# hand_main_v2.net
KiCad netlist of a schematic drawn in Altium Designer
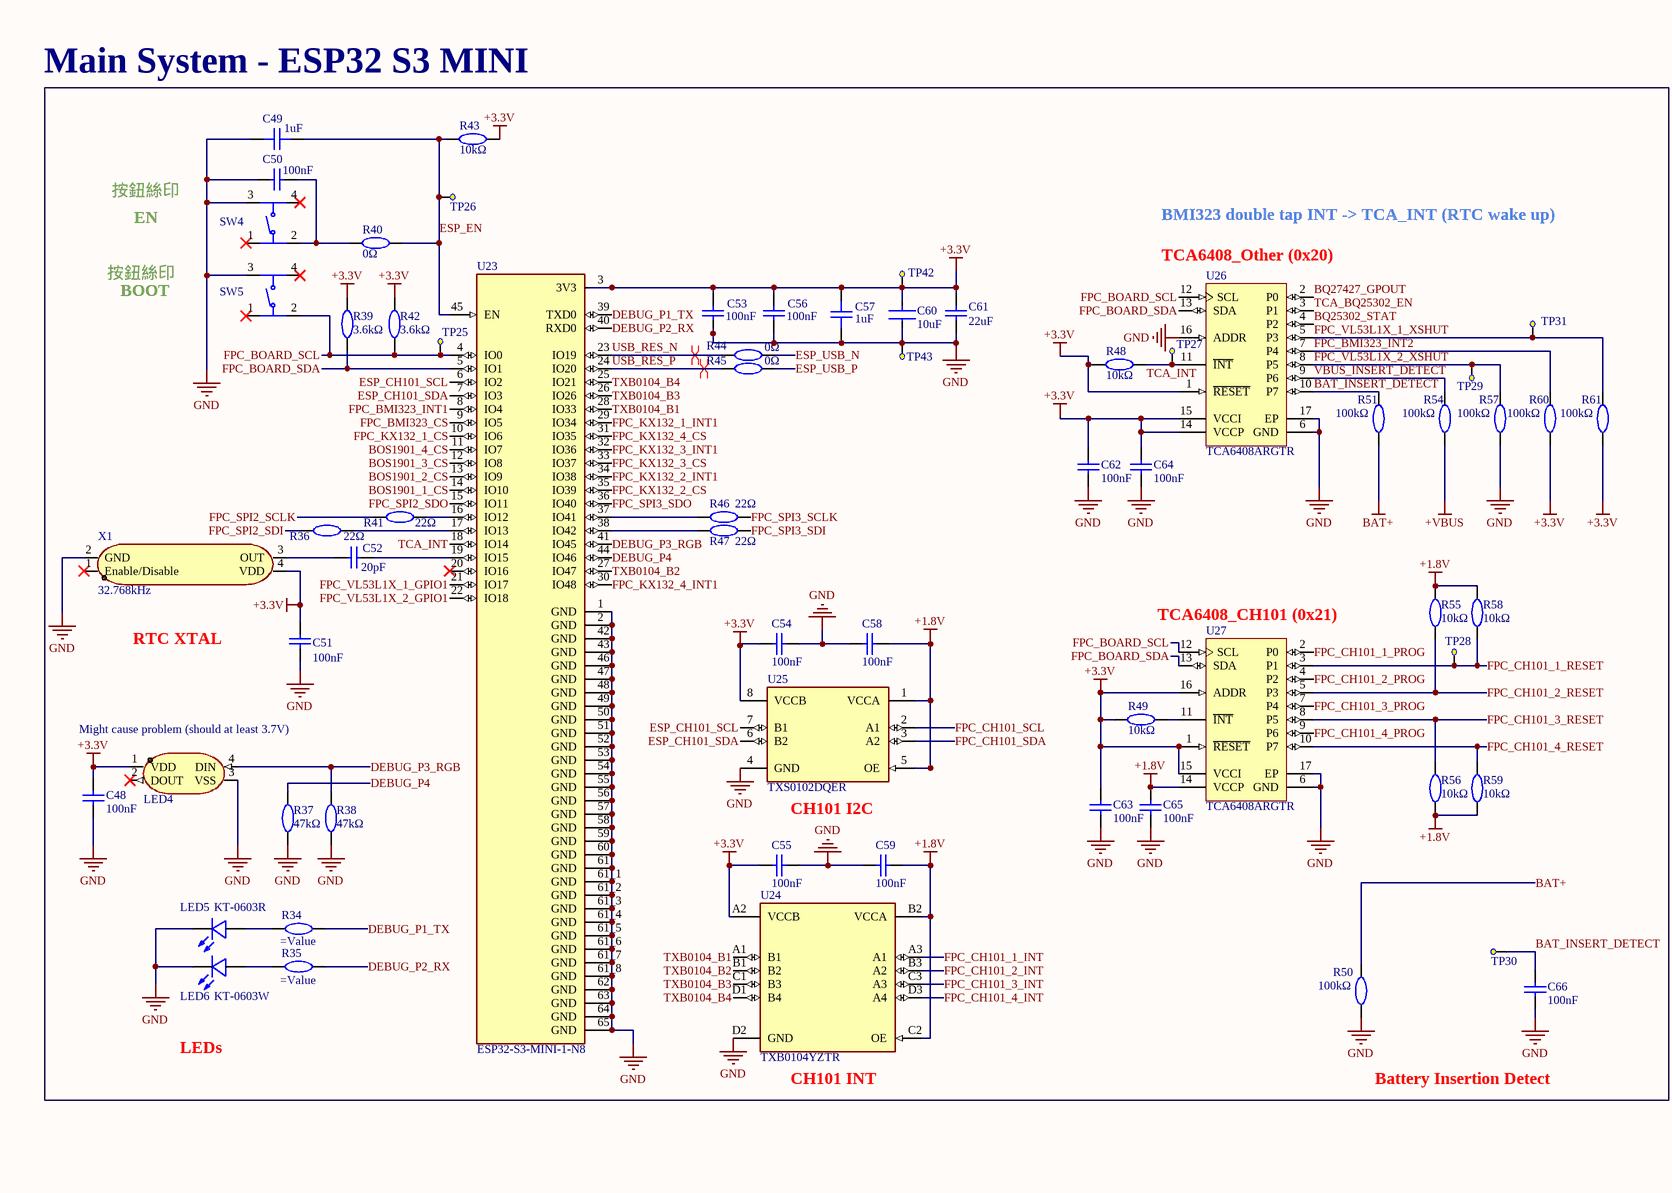
[diagram p0: hand_main_v2.SchDoc, left]
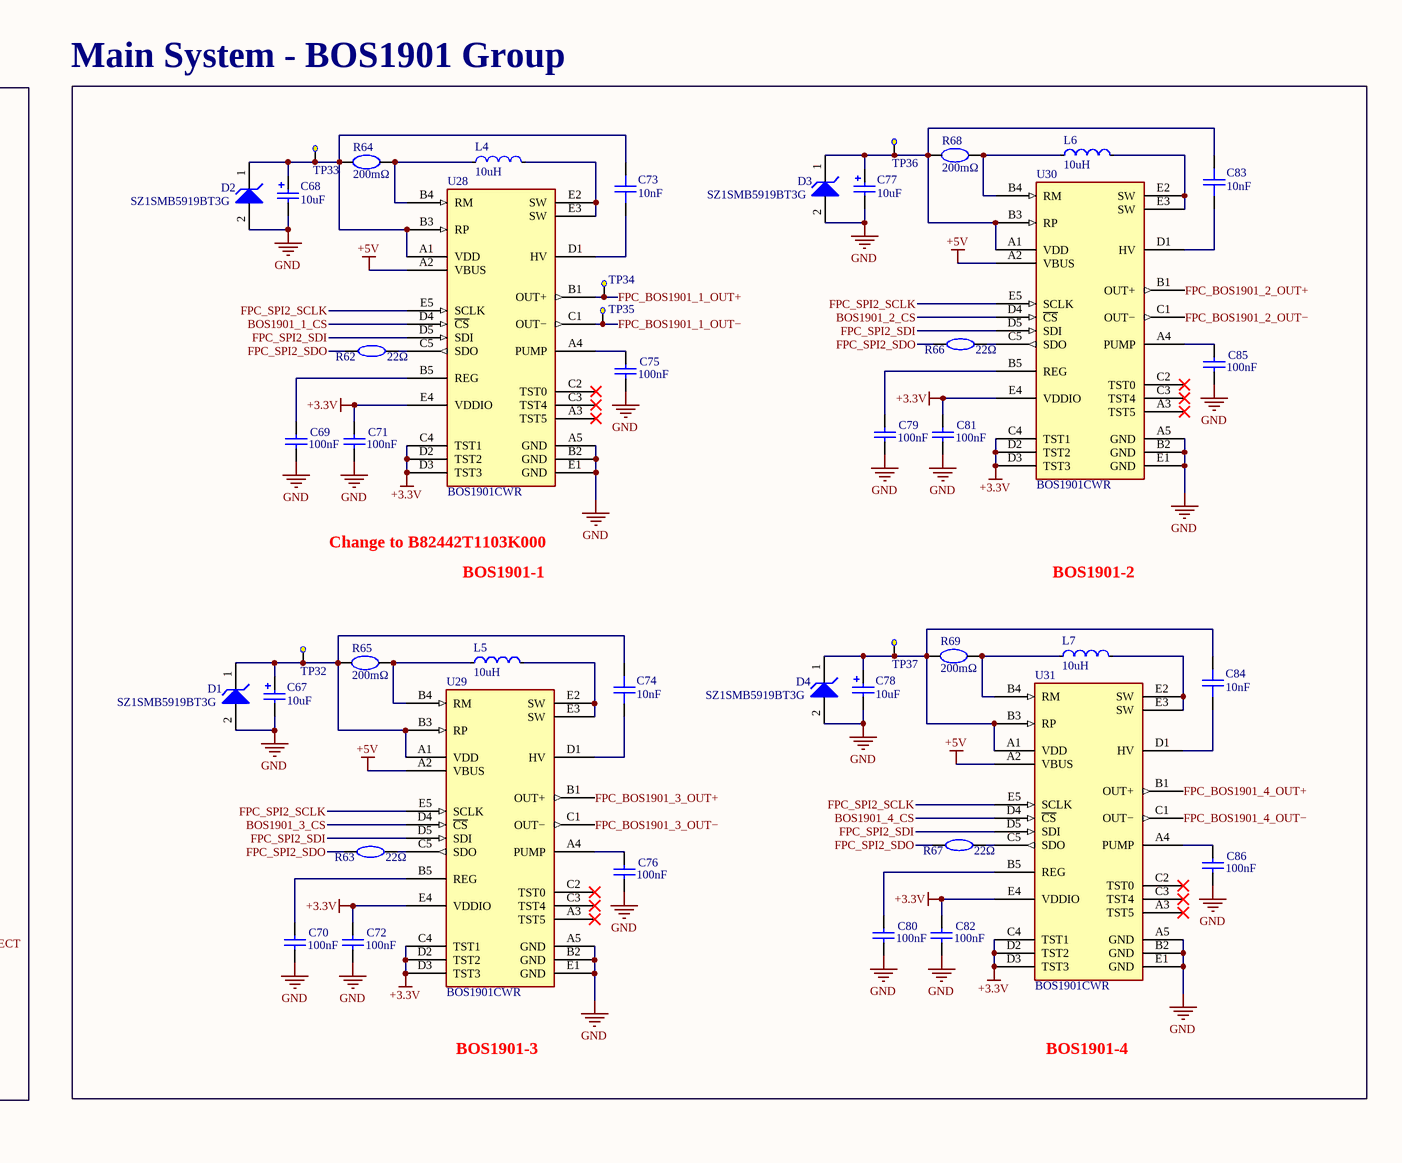
[diagram p1: hand_main_v2.SchDoc, middle]
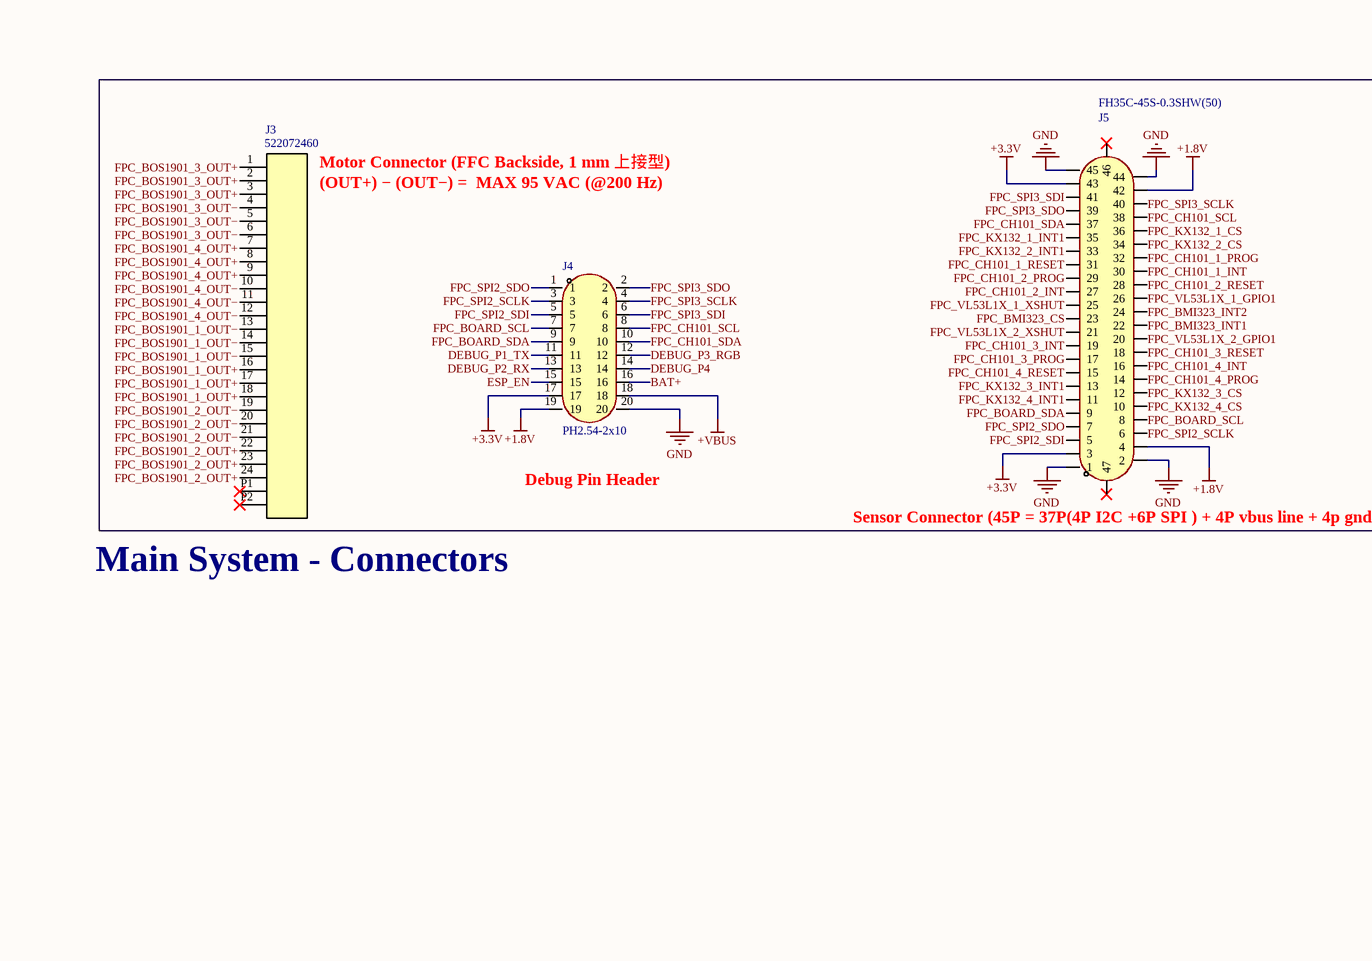
[diagram p2: hand_main_v2.SchDoc, right]

(export (version "E")
  (design (tool "Eeschema 10.0.6"))
  (components
    (comp (ref "C48")
      (value "100nF")
      (footprint "CAPC1050X55X23NL05T13")
      (description "Chip Capacitor, 100 nF, +/- 10%, 16 V, -55 to 125 degC, 0402 (1005 Metric), RoHS, Tape and Reel")
      (fields (field (name "MANUFACTURER") "Samsung Electro-Mechanics"))
      (libsource (lib "hand_ad_lib") (part "CL05B104KO5NNNC"))
    )
    (comp (ref "C49")
      (value "1uF")
      (footprint "C0402")
      (description "MLCC, 1 uF, 25 V, ± 10%, X5R, 0402 [1005 Metric]")
      (fields
        (field (name "MANUFACTURER") "SAMSUNG(三星)")
        (field (name "MANUFACTURER PART") "CL05A105KA5NQNC")
        (field (name "NAME") "1uF")
      )
      (libsource (lib "hand_ad_lib") (part "CL05A105KA5NQNC"))
    )
    (comp (ref "C50")
      (value "100nF")
      (footprint "CAPC1050X55X23NL05T13")
      (description "Chip Capacitor, 100 nF, +/- 10%, 16 V, -55 to 125 degC, 0402 (1005 Metric), RoHS, Tape and Reel")
      (fields (field (name "MANUFACTURER") "Samsung Electro-Mechanics"))
      (libsource (lib "hand_ad_lib") (part "CL05B104KO5NNNC"))
    )
    (comp (ref "C51")
      (value "100nF")
      (footprint "CAPC1050X55X23NL05T13")
      (description "Chip Capacitor, 100 nF, +/- 10%, 16 V, -55 to 125 degC, 0402 (1005 Metric), RoHS, Tape and Reel")
      (fields (field (name "MANUFACTURER") "Samsung Electro-Mechanics"))
      (libsource (lib "hand_ad_lib") (part "CL05B104KO5NNNC"))
    )
    (comp (ref "C52")
      (value "20pF")
      (footprint "C0603")
      (description "MLCC, 20pF, 50 V, ± 5%, C0G, 0603 [1608 Metric]")
      (fields
        (field (name "MANUFACTURER") "SAMSUNG(三星)")
        (field (name "MANUFACTURER PART") "CL10C200JB8NNNC")
        (field (name "NAME") "20pF")
      )
      (libsource (lib "hand_ad_lib") (part "CL10C200JB8NNNC"))
    )
    (comp (ref "C53")
      (value "100nF")
      (footprint "CAPC1050X55X23NL05T13")
      (description "Chip Capacitor, 100 nF, +/- 10%, 16 V, -55 to 125 degC, 0402 (1005 Metric), RoHS, Tape and Reel")
      (fields (field (name "MANUFACTURER") "Samsung Electro-Mechanics"))
      (libsource (lib "hand_ad_lib") (part "CL05B104KO5NNNC"))
    )
    (comp (ref "C54")
      (value "100nF")
      (footprint "CAPC1050X55X23NL05T13")
      (description "Chip Capacitor, 100 nF, +/- 10%, 16 V, -55 to 125 degC, 0402 (1005 Metric), RoHS, Tape and Reel")
      (fields (field (name "MANUFACTURER") "Samsung Electro-Mechanics"))
      (libsource (lib "hand_ad_lib") (part "CL05B104KO5NNNC"))
    )
    (comp (ref "C55")
      (value "100nF")
      (footprint "CAPC1050X55X23NL05T13")
      (description "Chip Capacitor, 100 nF, +/- 10%, 16 V, -55 to 125 degC, 0402 (1005 Metric), RoHS, Tape and Reel")
      (fields (field (name "MANUFACTURER") "Samsung Electro-Mechanics"))
      (libsource (lib "hand_ad_lib") (part "CL05B104KO5NNNC"))
    )
    (comp (ref "C56")
      (value "100nF")
      (footprint "CAPC1050X55X23NL05T13")
      (description "Chip Capacitor, 100 nF, +/- 10%, 16 V, -55 to 125 degC, 0402 (1005 Metric), RoHS, Tape and Reel")
      (fields (field (name "MANUFACTURER") "Samsung Electro-Mechanics"))
      (libsource (lib "hand_ad_lib") (part "CL05B104KO5NNNC"))
    )
    (comp (ref "C57")
      (value "1uF")
      (footprint "C0402")
      (description "MLCC, 1 uF, 25 V, ± 10%, X5R, 0402 [1005 Metric]")
      (fields
        (field (name "MANUFACTURER") "SAMSUNG(三星)")
        (field (name "MANUFACTURER PART") "CL05A105KA5NQNC")
        (field (name "NAME") "1uF")
      )
      (libsource (lib "hand_ad_lib") (part "CL05A105KA5NQNC"))
    )
    (comp (ref "C58")
      (value "100nF")
      (footprint "CAPC1050X55X23NL05T13")
      (description "Chip Capacitor, 100 nF, +/- 10%, 16 V, -55 to 125 degC, 0402 (1005 Metric), RoHS, Tape and Reel")
      (fields (field (name "MANUFACTURER") "Samsung Electro-Mechanics"))
      (libsource (lib "hand_ad_lib") (part "CL05B104KO5NNNC"))
    )
    (comp (ref "C59")
      (value "100nF")
      (footprint "CAPC1050X55X23NL05T13")
      (description "Chip Capacitor, 100 nF, +/- 10%, 16 V, -55 to 125 degC, 0402 (1005 Metric), RoHS, Tape and Reel")
      (fields (field (name "MANUFACTURER") "Samsung Electro-Mechanics"))
      (libsource (lib "hand_ad_lib") (part "CL05B104KO5NNNC"))
    )
    (comp (ref "C60")
      (value "10uF")
      (footprint "FP-CL10-IPC_A")
      (description "Cap Ceramic 10uF 25V X5R ±20% Pad SMD 0603 +85°C T/R")
      (fields (field (name "TOLERANCE") "20%"))
      (libsource (lib "hand_ad_lib") (part "CL10A106MA8NRNC"))
    )
    (comp (ref "C61")
      (value "22uF")
      (footprint "CAPC2013X140X45ML15T25")
      (description "Multi-layer Ceramic Capacitor, 22 uF, -55 to 85 degC, 2-Pin SMD (0805), RoHS, Tape and Reel")
      (fields (field (name "MANUFACTURER") "Samsung Electro-Mechanics") (field (name "TOLERANCE") "±20%"))
      (libsource (lib "hand_ad_lib") (part "CL21A226MAQNNNE"))
    )
    (comp (ref "C62")
      (value "100nF")
      (footprint "CAPC1050X55X23NL05T13")
      (description "Chip Capacitor, 100 nF, +/- 10%, 16 V, -55 to 125 degC, 0402 (1005 Metric), RoHS, Tape and Reel")
      (fields (field (name "MANUFACTURER") "Samsung Electro-Mechanics"))
      (libsource (lib "hand_ad_lib") (part "CL05B104KO5NNNC"))
    )
    (comp (ref "C63")
      (value "100nF")
      (footprint "CAPC1050X55X23NL05T13")
      (description "Chip Capacitor, 100 nF, +/- 10%, 16 V, -55 to 125 degC, 0402 (1005 Metric), RoHS, Tape and Reel")
      (fields (field (name "MANUFACTURER") "Samsung Electro-Mechanics"))
      (libsource (lib "hand_ad_lib") (part "CL05B104KO5NNNC"))
    )
    (comp (ref "C64")
      (value "100nF")
      (footprint "CAPC1050X55X23NL05T13")
      (description "Chip Capacitor, 100 nF, +/- 10%, 16 V, -55 to 125 degC, 0402 (1005 Metric), RoHS, Tape and Reel")
      (fields (field (name "MANUFACTURER") "Samsung Electro-Mechanics"))
      (libsource (lib "hand_ad_lib") (part "CL05B104KO5NNNC"))
    )
    (comp (ref "C65")
      (value "100nF")
      (footprint "CAPC1050X55X23NL05T13")
      (description "Chip Capacitor, 100 nF, +/- 10%, 16 V, -55 to 125 degC, 0402 (1005 Metric), RoHS, Tape and Reel")
      (fields (field (name "MANUFACTURER") "Samsung Electro-Mechanics"))
      (libsource (lib "hand_ad_lib") (part "CL05B104KO5NNNC"))
    )
    (comp (ref "C66")
      (value "100nF")
      (footprint "CAPC1050X55X23NL05T13")
      (description "Chip Capacitor, 100 nF, +/- 10%, 16 V, -55 to 125 degC, 0402 (1005 Metric), RoHS, Tape and Reel")
      (fields (field (name "MANUFACTURER") "Samsung Electro-Mechanics"))
      (libsource (lib "hand_ad_lib") (part "CL05B104KO5NNNC"))
    )
    (comp (ref "C67")
      (value "10uF")
      (footprint "CAP-SMD_L3.2-W1.6-RD-C7171")
      (fields
        (field (name "MANUFACTURER") "Kyocera AVX")
        (field (name "MANUFACTURER PART") "TAJA106K016RNJ")
        (field (name "TOLERANCE") "±10%")
        (field (name "NAME") "10uF")
      )
      (libsource (lib "hand_ad_lib") (part "TAJA106K016RNJ"))
    )
    (comp (ref "C68")
      (value "10uF")
      (footprint "CAP-SMD_L3.2-W1.6-RD-C7171")
      (fields
        (field (name "MANUFACTURER") "Kyocera AVX")
        (field (name "MANUFACTURER PART") "TAJA106K016RNJ")
        (field (name "TOLERANCE") "±10%")
        (field (name "NAME") "10uF")
      )
      (libsource (lib "hand_ad_lib") (part "TAJA106K016RNJ"))
    )
    (comp (ref "C69")
      (value "100nF")
      (footprint "CAPC1050X55X23NL05T13")
      (description "Chip Capacitor, 100 nF, +/- 10%, 16 V, -55 to 125 degC, 0402 (1005 Metric), RoHS, Tape and Reel")
      (fields (field (name "MANUFACTURER") "Samsung Electro-Mechanics"))
      (libsource (lib "hand_ad_lib") (part "CL05B104KO5NNNC"))
    )
    (comp (ref "C70")
      (value "100nF")
      (footprint "CAPC1050X55X23NL05T13")
      (description "Chip Capacitor, 100 nF, +/- 10%, 16 V, -55 to 125 degC, 0402 (1005 Metric), RoHS, Tape and Reel")
      (fields (field (name "MANUFACTURER") "Samsung Electro-Mechanics"))
      (libsource (lib "hand_ad_lib") (part "CL05B104KO5NNNC"))
    )
    (comp (ref "C71")
      (value "100nF")
      (footprint "CAPC1050X55X23NL05T13")
      (description "Chip Capacitor, 100 nF, +/- 10%, 16 V, -55 to 125 degC, 0402 (1005 Metric), RoHS, Tape and Reel")
      (fields (field (name "MANUFACTURER") "Samsung Electro-Mechanics"))
      (libsource (lib "hand_ad_lib") (part "CL05B104KO5NNNC"))
    )
    (comp (ref "C72")
      (value "100nF")
      (footprint "CAPC1050X55X23NL05T13")
      (description "Chip Capacitor, 100 nF, +/- 10%, 16 V, -55 to 125 degC, 0402 (1005 Metric), RoHS, Tape and Reel")
      (fields (field (name "MANUFACTURER") "Samsung Electro-Mechanics"))
      (libsource (lib "hand_ad_lib") (part "CL05B104KO5NNNC"))
    )
    (comp (ref "C73")
      (value "10nF")
      (footprint "C1206")
      (description "Cap Ceramic 0.01uF 250V C0G 5% SMD 1206 125°C Embossed T/R")
      (fields
        (field (name "MANUFACTURER") "muRata(村田)")
        (field (name "MANUFACTURER PART") "GCM31B5C2E103JX01L")
        (field (name "NAME") "10nF")
      )
      (libsource (lib "hand_ad_lib") (part "GCM31B5C2E103JX01L"))
    )
    (comp (ref "C74")
      (value "10nF")
      (footprint "C1206")
      (description "Cap Ceramic 0.01uF 250V C0G 5% SMD 1206 125°C Embossed T/R")
      (fields
        (field (name "MANUFACTURER") "muRata(村田)")
        (field (name "MANUFACTURER PART") "GCM31B5C2E103JX01L")
        (field (name "NAME") "10nF")
      )
      (libsource (lib "hand_ad_lib") (part "GCM31B5C2E103JX01L"))
    )
    (comp (ref "C75")
      (value "100nF")
      (footprint "CAPC1050X55X23NL05T13")
      (description "Chip Capacitor, 100 nF, +/- 10%, 16 V, -55 to 125 degC, 0402 (1005 Metric), RoHS, Tape and Reel")
      (fields (field (name "MANUFACTURER") "Samsung Electro-Mechanics"))
      (libsource (lib "hand_ad_lib") (part "CL05B104KO5NNNC"))
    )
    (comp (ref "C76")
      (value "100nF")
      (footprint "CAPC1050X55X23NL05T13")
      (description "Chip Capacitor, 100 nF, +/- 10%, 16 V, -55 to 125 degC, 0402 (1005 Metric), RoHS, Tape and Reel")
      (fields (field (name "MANUFACTURER") "Samsung Electro-Mechanics"))
      (libsource (lib "hand_ad_lib") (part "CL05B104KO5NNNC"))
    )
    (comp (ref "C77")
      (value "10uF")
      (footprint "CAP-SMD_L3.2-W1.6-RD-C7171")
      (fields
        (field (name "MANUFACTURER") "Kyocera AVX")
        (field (name "MANUFACTURER PART") "TAJA106K016RNJ")
        (field (name "TOLERANCE") "±10%")
        (field (name "NAME") "10uF")
      )
      (libsource (lib "hand_ad_lib") (part "TAJA106K016RNJ"))
    )
    (comp (ref "C78")
      (value "10uF")
      (footprint "CAP-SMD_L3.2-W1.6-RD-C7171")
      (fields
        (field (name "MANUFACTURER") "Kyocera AVX")
        (field (name "MANUFACTURER PART") "TAJA106K016RNJ")
        (field (name "TOLERANCE") "±10%")
        (field (name "NAME") "10uF")
      )
      (libsource (lib "hand_ad_lib") (part "TAJA106K016RNJ"))
    )
    (comp (ref "C79")
      (value "100nF")
      (footprint "CAPC1050X55X23NL05T13")
      (description "Chip Capacitor, 100 nF, +/- 10%, 16 V, -55 to 125 degC, 0402 (1005 Metric), RoHS, Tape and Reel")
      (fields (field (name "MANUFACTURER") "Samsung Electro-Mechanics"))
      (libsource (lib "hand_ad_lib") (part "CL05B104KO5NNNC"))
    )
    (comp (ref "C80")
      (value "100nF")
      (footprint "CAPC1050X55X23NL05T13")
      (description "Chip Capacitor, 100 nF, +/- 10%, 16 V, -55 to 125 degC, 0402 (1005 Metric), RoHS, Tape and Reel")
      (fields (field (name "MANUFACTURER") "Samsung Electro-Mechanics"))
      (libsource (lib "hand_ad_lib") (part "CL05B104KO5NNNC"))
    )
    (comp (ref "C81")
      (value "100nF")
      (footprint "CAPC1050X55X23NL05T13")
      (description "Chip Capacitor, 100 nF, +/- 10%, 16 V, -55 to 125 degC, 0402 (1005 Metric), RoHS, Tape and Reel")
      (fields (field (name "MANUFACTURER") "Samsung Electro-Mechanics"))
      (libsource (lib "hand_ad_lib") (part "CL05B104KO5NNNC"))
    )
    (comp (ref "C82")
      (value "100nF")
      (footprint "CAPC1050X55X23NL05T13")
      (description "Chip Capacitor, 100 nF, +/- 10%, 16 V, -55 to 125 degC, 0402 (1005 Metric), RoHS, Tape and Reel")
      (fields (field (name "MANUFACTURER") "Samsung Electro-Mechanics"))
      (libsource (lib "hand_ad_lib") (part "CL05B104KO5NNNC"))
    )
    (comp (ref "C83")
      (value "10nF")
      (footprint "C1206")
      (description "Cap Ceramic 0.01uF 250V C0G 5% SMD 1206 125°C Embossed T/R")
      (fields
        (field (name "MANUFACTURER") "muRata(村田)")
        (field (name "MANUFACTURER PART") "GCM31B5C2E103JX01L")
        (field (name "NAME") "10nF")
      )
      (libsource (lib "hand_ad_lib") (part "GCM31B5C2E103JX01L"))
    )
    (comp (ref "C84")
      (value "10nF")
      (footprint "C1206")
      (description "Cap Ceramic 0.01uF 250V C0G 5% SMD 1206 125°C Embossed T/R")
      (fields
        (field (name "MANUFACTURER") "muRata(村田)")
        (field (name "MANUFACTURER PART") "GCM31B5C2E103JX01L")
        (field (name "NAME") "10nF")
      )
      (libsource (lib "hand_ad_lib") (part "GCM31B5C2E103JX01L"))
    )
    (comp (ref "C85")
      (value "100nF")
      (footprint "CAPC1050X55X23NL05T13")
      (description "Chip Capacitor, 100 nF, +/- 10%, 16 V, -55 to 125 degC, 0402 (1005 Metric), RoHS, Tape and Reel")
      (fields (field (name "MANUFACTURER") "Samsung Electro-Mechanics"))
      (libsource (lib "hand_ad_lib") (part "CL05B104KO5NNNC"))
    )
    (comp (ref "C86")
      (value "100nF")
      (footprint "CAPC1050X55X23NL05T13")
      (description "Chip Capacitor, 100 nF, +/- 10%, 16 V, -55 to 125 degC, 0402 (1005 Metric), RoHS, Tape and Reel")
      (fields (field (name "MANUFACTURER") "Samsung Electro-Mechanics"))
      (libsource (lib "hand_ad_lib") (part "CL05B104KO5NNNC"))
    )
    (comp (ref "D1")
      (value "SZ1SMB5919BT3G")
      (footprint "ONSC-SMB-2-403A-03_H_V")
      (description "3 W Zener Voltage Regulator, 2-Pin SMB, Pb-Free, Tape and Reel")
      (fields (field (name "MANUFACTURER") "On Semiconductor"))
      (libsource (lib "hand_ad_lib") (part "SZ1SMB5919BT3G"))
    )
    (comp (ref "D2")
      (value "SZ1SMB5919BT3G")
      (footprint "ONSC-SMB-2-403A-03_H_V")
      (description "3 W Zener Voltage Regulator, 2-Pin SMB, Pb-Free, Tape and Reel")
      (fields (field (name "MANUFACTURER") "On Semiconductor"))
      (libsource (lib "hand_ad_lib") (part "SZ1SMB5919BT3G"))
    )
    (comp (ref "D3")
      (value "SZ1SMB5919BT3G")
      (footprint "ONSC-SMB-2-403A-03_H_V")
      (description "3 W Zener Voltage Regulator, 2-Pin SMB, Pb-Free, Tape and Reel")
      (fields (field (name "MANUFACTURER") "On Semiconductor"))
      (libsource (lib "hand_ad_lib") (part "SZ1SMB5919BT3G"))
    )
    (comp (ref "D4")
      (value "SZ1SMB5919BT3G")
      (footprint "ONSC-SMB-2-403A-03_H_V")
      (description "3 W Zener Voltage Regulator, 2-Pin SMB, Pb-Free, Tape and Reel")
      (fields (field (name "MANUFACTURER") "On Semiconductor"))
      (libsource (lib "hand_ad_lib") (part "SZ1SMB5919BT3G"))
    )
    (comp (ref "J3")
      (value "522072460")
      (footprint "CON_522072460_MOL")
      (description "FFC 1mm 24P")
      (libsource (lib "hand_ad_lib") (part "522072460"))
    )
    (comp (ref "J4")
      (value "PH2.54-2x10")
      (footprint "HDR-TH_20P-P2.54-V-M-R2-C10-S2.54")
      (description "Pin Header 2.54mm, 2x10")
      (fields (field (name "MANUFACTURER") "ZHOURI(洲日)") (field (name "NAME") "PH2.54-2x10"))
      (libsource (lib "hand_ad_lib") (part "PH2.54-2x10"))
    )
    (comp (ref "J5")
      (value "FH35C-45S-0.3SHW(50)")
      (footprint "FPC-SMD_FH35C-45S-0.3SHW-50")
      (description "FPC Connector, 45P, 0.3mm, Right Angle, Double Side Connection")
      (fields (field (name "MANUFACTURER") "HRS(广濑)") (field (name "NAME") "FH35C-45S-0.3SHW(50)"))
      (libsource (lib "hand_ad_lib") (part "FH35C-45S-0.3SHW(50)"))
    )
    (comp (ref "L4")
      (value "10uH")
      (footprint "IND-SMD_L7.8-W7.0-A")
      (description "Ind Power Unshielded Wirewound 10uH 10% 2.52MHz 2.3A Carrier T/R")
      (fields
        (field (name "MANUFACTURER") "Sumida(胜美达)")
        (field (name "MANUFACTURER PART") "CD75T125NP-100KC")
        (field (name "NAME") "10uH")
      )
      (libsource (lib "hand_ad_lib") (part "CD75T125NP-100KC"))
    )
    (comp (ref "L5")
      (value "10uH")
      (footprint "IND-SMD_L7.8-W7.0-A")
      (description "Ind Power Unshielded Wirewound 10uH 10% 2.52MHz 2.3A Carrier T/R")
      (fields
        (field (name "MANUFACTURER") "Sumida(胜美达)")
        (field (name "MANUFACTURER PART") "CD75T125NP-100KC")
        (field (name "NAME") "10uH")
      )
      (libsource (lib "hand_ad_lib") (part "CD75T125NP-100KC"))
    )
    (comp (ref "L6")
      (value "10uH")
      (footprint "IND-SMD_L7.8-W7.0-A")
      (description "Ind Power Unshielded Wirewound 10uH 10% 2.52MHz 2.3A Carrier T/R")
      (fields
        (field (name "MANUFACTURER") "Sumida(胜美达)")
        (field (name "MANUFACTURER PART") "CD75T125NP-100KC")
        (field (name "NAME") "10uH")
      )
      (libsource (lib "hand_ad_lib") (part "CD75T125NP-100KC"))
    )
    (comp (ref "L7")
      (value "10uH")
      (footprint "IND-SMD_L7.8-W7.0-A")
      (description "Ind Power Unshielded Wirewound 10uH 10% 2.52MHz 2.3A Carrier T/R")
      (fields
        (field (name "MANUFACTURER") "Sumida(胜美达)")
        (field (name "MANUFACTURER PART") "CD75T125NP-100KC")
        (field (name "NAME") "10uH")
      )
      (libsource (lib "hand_ad_lib") (part "CD75T125NP-100KC"))
    )
    (comp (ref "LED4")
      (value "WS2812B-MINI-V3/W")
      (footprint "LED-SMD_4P-L3.5-W3.5-TL_WS2812B")
      (fields (field (name "MANUFACTURER") "worldsemi"))
      (libsource (lib "hand_ad_lib") (part "WS2812B-MINI-V3/W"))
    )
    (comp (ref "LED5")
      (value "KT-0603R")
      (footprint "LED0603-RD")
      (description "LED, Red 0603")
      (fields (field (name "MANUFACTURER") "KENTO") (field (name "NAME") "KT-0603R"))
      (libsource (lib "hand_ad_lib") (part "KT-0603R"))
    )
    (comp (ref "LED6")
      (value "KT-0603W")
      (footprint "LED0603-R-RD_WHITE")
      (description "LED, White 0603")
      (fields (field (name "MANUFACTURER") "KENTO") (field (name "NAME") "KT-0603W"))
      (libsource (lib "hand_ad_lib") (part "KT-0603W"))
    )
    (comp (ref "R34")
      (value "~")
      (footprint "R0402")
      (description "Resistor, Res Thick Film 0402 1K Ohm 1% 0.063W(1/16W) ±100ppm/°C Pad SMD T/R")
      (fields
        (field (name "MANUFACTURER") "UNI-ROYAL(厚声)")
        (field (name "MANUFACTURER PART") "0402WGF1001TCE")
      )
      (libsource (lib "hand_ad_lib") (part "0402WGF1001TCE"))
    )
    (comp (ref "R35")
      (value "~")
      (footprint "R0402")
      (description "Resistor, Res Thick Film 0402 1K Ohm 1% 0.063W(1/16W) ±100ppm/°C Pad SMD T/R")
      (fields
        (field (name "MANUFACTURER") "UNI-ROYAL(厚声)")
        (field (name "MANUFACTURER PART") "0402WGF1001TCE")
      )
      (libsource (lib "hand_ad_lib") (part "0402WGF1001TCE"))
    )
    (comp (ref "R36")
      (value "22Ω")
      (footprint "R0402")
      (description "Resistor, Res Thick Film 0402 22 Ohm 1% 0.063W(1/16W) ±200ppm/°C Pad SMD T/R")
      (fields
        (field (name "MANUFACTURER") "UNI-ROYAL(厚声)")
        (field (name "MANUFACTURER PART") "0402WGF220JTCE")
        (field (name "NAME") "22Ω")
      )
      (libsource (lib "hand_ad_lib") (part "0402WGF220JTCE"))
    )
    (comp (ref "R37")
      (value "47kΩ")
      (footprint "R0402")
      (description "Resistor, Res Thick Film 0402 47K Ohm 1% 0.063W(1/16W) ±100ppm/°C Pad SMD T/R")
      (fields
        (field (name "MANUFACTURER") "UNI-ROYAL(厚声)")
        (field (name "MANUFACTURER PART") "0402WGF4702TCE")
        (field (name "NAME") "47kΩ")
      )
      (libsource (lib "hand_ad_lib") (part "0402WGF4702TCE"))
    )
    (comp (ref "R38")
      (value "47kΩ")
      (footprint "R0402")
      (description "Resistor, Res Thick Film 0402 47K Ohm 1% 0.063W(1/16W) ±100ppm/°C Pad SMD T/R")
      (fields
        (field (name "MANUFACTURER") "UNI-ROYAL(厚声)")
        (field (name "MANUFACTURER PART") "0402WGF4702TCE")
        (field (name "NAME") "47kΩ")
      )
      (libsource (lib "hand_ad_lib") (part "0402WGF4702TCE"))
    )
    (comp (ref "R39")
      (value "3.6kΩ")
      (footprint "R0603")
      (description "Resistor, Res Thick Film 0603 3.6K Ohm 1% 0.1W ±100ppm/°C Pad SMD T/R")
      (fields
        (field (name "MANUFACTURER") "UNI-ROYAL(厚声)")
        (field (name "MANUFACTURER PART") "0603WAF3601T5E")
        (field (name "NAME") "3.6kΩ")
      )
      (libsource (lib "hand_ad_lib") (part "0603WAF3601T5E"))
    )
    (comp (ref "R40")
      (value "0Ω")
      (footprint "R0402")
      (description "Resistor, Res Thick Film 0402 0 Ohm 1% 0.063W(1/16W) ±800ppm/°C Pad SMD T/R")
      (fields
        (field (name "MANUFACTURER") "UNI-ROYAL(厚声)")
        (field (name "MANUFACTURER PART") "0402WGF0000TCE")
        (field (name "NAME") "0Ω")
      )
      (libsource (lib "hand_ad_lib") (part "0402WGF0000TCE"))
    )
    (comp (ref "R41")
      (value "22Ω")
      (footprint "R0402")
      (description "Resistor, Res Thick Film 0402 22 Ohm 1% 0.063W(1/16W) ±200ppm/°C Pad SMD T/R")
      (fields
        (field (name "MANUFACTURER") "UNI-ROYAL(厚声)")
        (field (name "MANUFACTURER PART") "0402WGF220JTCE")
        (field (name "NAME") "22Ω")
      )
      (libsource (lib "hand_ad_lib") (part "0402WGF220JTCE"))
    )
    (comp (ref "R42")
      (value "3.6kΩ")
      (footprint "R0603")
      (description "Resistor, Res Thick Film 0603 3.6K Ohm 1% 0.1W ±100ppm/°C Pad SMD T/R")
      (fields
        (field (name "MANUFACTURER") "UNI-ROYAL(厚声)")
        (field (name "MANUFACTURER PART") "0603WAF3601T5E")
        (field (name "NAME") "3.6kΩ")
      )
      (libsource (lib "hand_ad_lib") (part "0603WAF3601T5E"))
    )
    (comp (ref "R43")
      (value "10kΩ")
      (footprint "R0402")
      (description "Resistor, Res Thick Film 0402 10K Ohm 1% 0.063W(1/16W) ±100ppm/°C Pad SMD T/R")
      (fields
        (field (name "MANUFACTURER") "UNI-ROYAL(厚声)")
        (field (name "MANUFACTURER PART") "0402WGF1002TCE")
        (field (name "NAME") "10kΩ")
      )
      (libsource (lib "hand_ad_lib") (part "0402WGF1002TCE"))
    )
    (comp (ref "R44")
      (value "0Ω")
      (footprint "R0402")
      (description "Resistor, Res Thick Film 0402 0 Ohm 1% 0.063W(1/16W) ±800ppm/°C Pad SMD T/R")
      (fields
        (field (name "MANUFACTURER") "UNI-ROYAL(厚声)")
        (field (name "MANUFACTURER PART") "0402WGF0000TCE")
        (field (name "NAME") "0Ω")
      )
      (libsource (lib "hand_ad_lib") (part "0402WGF0000TCE"))
    )
    (comp (ref "R45")
      (value "0Ω")
      (footprint "R0402")
      (description "Resistor, Res Thick Film 0402 0 Ohm 1% 0.063W(1/16W) ±800ppm/°C Pad SMD T/R")
      (fields
        (field (name "MANUFACTURER") "UNI-ROYAL(厚声)")
        (field (name "MANUFACTURER PART") "0402WGF0000TCE")
        (field (name "NAME") "0Ω")
      )
      (libsource (lib "hand_ad_lib") (part "0402WGF0000TCE"))
    )
    (comp (ref "R46")
      (value "22Ω")
      (footprint "R0402")
      (description "Resistor, Res Thick Film 0402 22 Ohm 1% 0.063W(1/16W) ±200ppm/°C Pad SMD T/R")
      (fields
        (field (name "MANUFACTURER") "UNI-ROYAL(厚声)")
        (field (name "MANUFACTURER PART") "0402WGF220JTCE")
        (field (name "NAME") "22Ω")
      )
      (libsource (lib "hand_ad_lib") (part "0402WGF220JTCE"))
    )
    (comp (ref "R47")
      (value "22Ω")
      (footprint "R0402")
      (description "Resistor, Res Thick Film 0402 22 Ohm 1% 0.063W(1/16W) ±200ppm/°C Pad SMD T/R")
      (fields
        (field (name "MANUFACTURER") "UNI-ROYAL(厚声)")
        (field (name "MANUFACTURER PART") "0402WGF220JTCE")
        (field (name "NAME") "22Ω")
      )
      (libsource (lib "hand_ad_lib") (part "0402WGF220JTCE"))
    )
    (comp (ref "R48")
      (value "10kΩ")
      (footprint "R0402")
      (description "Resistor, Res Thick Film 0402 10K Ohm 1% 0.063W(1/16W) ±100ppm/°C Pad SMD T/R")
      (fields
        (field (name "MANUFACTURER") "UNI-ROYAL(厚声)")
        (field (name "MANUFACTURER PART") "0402WGF1002TCE")
        (field (name "NAME") "10kΩ")
      )
      (libsource (lib "hand_ad_lib") (part "0402WGF1002TCE"))
    )
    (comp (ref "R49")
      (value "10kΩ")
      (footprint "R0402")
      (description "Resistor, Res Thick Film 0402 10K Ohm 1% 0.063W(1/16W) ±100ppm/°C Pad SMD T/R")
      (fields
        (field (name "MANUFACTURER") "UNI-ROYAL(厚声)")
        (field (name "MANUFACTURER PART") "0402WGF1002TCE")
        (field (name "NAME") "10kΩ")
      )
      (libsource (lib "hand_ad_lib") (part "0402WGF1002TCE"))
    )
    (comp (ref "R50")
      (value "100kΩ")
      (footprint "R0402")
      (description "Resistor, Res Thick Film 0402 100K Ohm 1% 0.063W(1/16W) ±100ppm/°C Pad SMD T/R")
      (fields
        (field (name "MANUFACTURER") "UNI-ROYAL(厚声)")
        (field (name "MANUFACTURER PART") "0402WGF1003TCE")
        (field (name "NAME") "100kΩ")
      )
      (libsource (lib "hand_ad_lib") (part "0402WGF1003TCE"))
    )
    (comp (ref "R51")
      (value "100kΩ")
      (footprint "R0402")
      (description "Resistor, Res Thick Film 0402 100K Ohm 1% 0.063W(1/16W) ±100ppm/°C Pad SMD T/R")
      (fields
        (field (name "MANUFACTURER") "UNI-ROYAL(厚声)")
        (field (name "MANUFACTURER PART") "0402WGF1003TCE")
        (field (name "NAME") "100kΩ")
      )
      (libsource (lib "hand_ad_lib") (part "0402WGF1003TCE"))
    )
    (comp (ref "R54")
      (value "100kΩ")
      (footprint "R0402")
      (description "Resistor, Res Thick Film 0402 100K Ohm 1% 0.063W(1/16W) ±100ppm/°C Pad SMD T/R")
      (fields
        (field (name "MANUFACTURER") "UNI-ROYAL(厚声)")
        (field (name "MANUFACTURER PART") "0402WGF1003TCE")
        (field (name "NAME") "100kΩ")
      )
      (libsource (lib "hand_ad_lib") (part "0402WGF1003TCE"))
    )
    (comp (ref "R55")
      (value "10kΩ")
      (footprint "R0402")
      (description "Resistor, Res Thick Film 0402 10K Ohm 1% 0.063W(1/16W) ±100ppm/°C Pad SMD T/R")
      (fields
        (field (name "MANUFACTURER") "UNI-ROYAL(厚声)")
        (field (name "MANUFACTURER PART") "0402WGF1002TCE")
        (field (name "NAME") "10kΩ")
      )
      (libsource (lib "hand_ad_lib") (part "0402WGF1002TCE"))
    )
    (comp (ref "R56")
      (value "10kΩ")
      (footprint "R0402")
      (description "Resistor, Res Thick Film 0402 10K Ohm 1% 0.063W(1/16W) ±100ppm/°C Pad SMD T/R")
      (fields
        (field (name "MANUFACTURER") "UNI-ROYAL(厚声)")
        (field (name "MANUFACTURER PART") "0402WGF1002TCE")
        (field (name "NAME") "10kΩ")
      )
      (libsource (lib "hand_ad_lib") (part "0402WGF1002TCE"))
    )
    (comp (ref "R57")
      (value "100kΩ")
      (footprint "R0402")
      (description "Resistor, Res Thick Film 0402 100K Ohm 1% 0.063W(1/16W) ±100ppm/°C Pad SMD T/R")
      (fields
        (field (name "MANUFACTURER") "UNI-ROYAL(厚声)")
        (field (name "MANUFACTURER PART") "0402WGF1003TCE")
        (field (name "NAME") "100kΩ")
      )
      (libsource (lib "hand_ad_lib") (part "0402WGF1003TCE"))
    )
    (comp (ref "R58")
      (value "10kΩ")
      (footprint "R0402")
      (description "Resistor, Res Thick Film 0402 10K Ohm 1% 0.063W(1/16W) ±100ppm/°C Pad SMD T/R")
      (fields
        (field (name "MANUFACTURER") "UNI-ROYAL(厚声)")
        (field (name "MANUFACTURER PART") "0402WGF1002TCE")
        (field (name "NAME") "10kΩ")
      )
      (libsource (lib "hand_ad_lib") (part "0402WGF1002TCE"))
    )
    (comp (ref "R59")
      (value "10kΩ")
      (footprint "R0402")
      (description "Resistor, Res Thick Film 0402 10K Ohm 1% 0.063W(1/16W) ±100ppm/°C Pad SMD T/R")
      (fields
        (field (name "MANUFACTURER") "UNI-ROYAL(厚声)")
        (field (name "MANUFACTURER PART") "0402WGF1002TCE")
        (field (name "NAME") "10kΩ")
      )
      (libsource (lib "hand_ad_lib") (part "0402WGF1002TCE"))
    )
    (comp (ref "R60")
      (value "100kΩ")
      (footprint "R0402")
      (description "Resistor, Res Thick Film 0402 100K Ohm 1% 0.063W(1/16W) ±100ppm/°C Pad SMD T/R")
      (fields
        (field (name "MANUFACTURER") "UNI-ROYAL(厚声)")
        (field (name "MANUFACTURER PART") "0402WGF1003TCE")
        (field (name "NAME") "100kΩ")
      )
      (libsource (lib "hand_ad_lib") (part "0402WGF1003TCE"))
    )
    (comp (ref "R61")
      (value "100kΩ")
      (footprint "R0402")
      (description "Resistor, Res Thick Film 0402 100K Ohm 1% 0.063W(1/16W) ±100ppm/°C Pad SMD T/R")
      (fields
        (field (name "MANUFACTURER") "UNI-ROYAL(厚声)")
        (field (name "MANUFACTURER PART") "0402WGF1003TCE")
        (field (name "NAME") "100kΩ")
      )
      (libsource (lib "hand_ad_lib") (part "0402WGF1003TCE"))
    )
    (comp (ref "R62")
      (value "22Ω")
      (footprint "R0402")
      (description "Resistor, Res Thick Film 0402 22 Ohm 1% 0.063W(1/16W) ±200ppm/°C Pad SMD T/R")
      (fields
        (field (name "MANUFACTURER") "UNI-ROYAL(厚声)")
        (field (name "MANUFACTURER PART") "0402WGF220JTCE")
        (field (name "NAME") "22Ω")
      )
      (libsource (lib "hand_ad_lib") (part "0402WGF220JTCE"))
    )
    (comp (ref "R63")
      (value "22Ω")
      (footprint "R0402")
      (description "Resistor, Res Thick Film 0402 22 Ohm 1% 0.063W(1/16W) ±200ppm/°C Pad SMD T/R")
      (fields
        (field (name "MANUFACTURER") "UNI-ROYAL(厚声)")
        (field (name "MANUFACTURER PART") "0402WGF220JTCE")
        (field (name "NAME") "22Ω")
      )
      (libsource (lib "hand_ad_lib") (part "0402WGF220JTCE"))
    )
    (comp (ref "R64")
      (value "200mΩ")
      (footprint "R1206")
      (fields
        (field (name "MANUFACTURER") "Milliohm(毫欧)")
        (field (name "MANUFACTURER PART") "HoYH1206-1W-200mR-1%")
        (field (name "TOLERANCE") "±1%")
        (field (name "NAME") "200mΩ")
      )
      (libsource (lib "hand_ad_lib") (part "HoYH1206-1W-200mR-1%"))
    )
    (comp (ref "R65")
      (value "200mΩ")
      (footprint "R1206")
      (fields
        (field (name "MANUFACTURER") "Milliohm(毫欧)")
        (field (name "MANUFACTURER PART") "HoYH1206-1W-200mR-1%")
        (field (name "TOLERANCE") "±1%")
        (field (name "NAME") "200mΩ")
      )
      (libsource (lib "hand_ad_lib") (part "HoYH1206-1W-200mR-1%"))
    )
    (comp (ref "R66")
      (value "22Ω")
      (footprint "R0402")
      (description "Resistor, Res Thick Film 0402 22 Ohm 1% 0.063W(1/16W) ±200ppm/°C Pad SMD T/R")
      (fields
        (field (name "MANUFACTURER") "UNI-ROYAL(厚声)")
        (field (name "MANUFACTURER PART") "0402WGF220JTCE")
        (field (name "NAME") "22Ω")
      )
      (libsource (lib "hand_ad_lib") (part "0402WGF220JTCE"))
    )
    (comp (ref "R67")
      (value "22Ω")
      (footprint "R0402")
      (description "Resistor, Res Thick Film 0402 22 Ohm 1% 0.063W(1/16W) ±200ppm/°C Pad SMD T/R")
      (fields
        (field (name "MANUFACTURER") "UNI-ROYAL(厚声)")
        (field (name "MANUFACTURER PART") "0402WGF220JTCE")
        (field (name "NAME") "22Ω")
      )
      (libsource (lib "hand_ad_lib") (part "0402WGF220JTCE"))
    )
    (comp (ref "R68")
      (value "200mΩ")
      (footprint "R1206")
      (fields
        (field (name "MANUFACTURER") "Milliohm(毫欧)")
        (field (name "MANUFACTURER PART") "HoYH1206-1W-200mR-1%")
        (field (name "TOLERANCE") "±1%")
        (field (name "NAME") "200mΩ")
      )
      (libsource (lib "hand_ad_lib") (part "HoYH1206-1W-200mR-1%"))
    )
    (comp (ref "R69")
      (value "200mΩ")
      (footprint "R1206")
      (fields
        (field (name "MANUFACTURER") "Milliohm(毫欧)")
        (field (name "MANUFACTURER PART") "HoYH1206-1W-200mR-1%")
        (field (name "TOLERANCE") "±1%")
        (field (name "NAME") "200mΩ")
      )
      (libsource (lib "hand_ad_lib") (part "HoYH1206-1W-200mR-1%"))
    )
    (comp (ref "SW4")
      (value "TS-1187A-B-A-B")
      (footprint "SW-SMD_4P-L5.1-W5.1-P3.70-LS6.5-TL-2")
      (description "Touch Button")
      (fields (field (name "MANUFACTURER") "XKB Connectivity(中国星坤)"))
      (libsource (lib "hand_ad_lib") (part "TS-1187A-B-A-B"))
    )
    (comp (ref "SW5")
      (value "TS-1187A-B-A-B")
      (footprint "SW-SMD_4P-L5.1-W5.1-P3.70-LS6.5-TL-2")
      (description "Touch Button, Boot")
      (fields (field (name "MANUFACTURER") "XKB Connectivity(中国星坤)"))
      (libsource (lib "hand_ad_lib") (part "TS-1187A-B-A-B"))
    )
    (comp (ref "TP25")
      (value "Test point")
      (footprint "Test_Point")
      (libsource (lib "hand_ad_lib") (part "Test_Point"))
    )
    (comp (ref "TP26")
      (value "Test point")
      (footprint "Test_Point")
      (libsource (lib "hand_ad_lib") (part "Test_Point"))
    )
    (comp (ref "TP27")
      (value "Test point")
      (footprint "Test_Point")
      (libsource (lib "hand_ad_lib") (part "Test_Point"))
    )
    (comp (ref "TP28")
      (value "Test point")
      (footprint "Test_Point")
      (libsource (lib "hand_ad_lib") (part "Test_Point"))
    )
    (comp (ref "TP29")
      (value "Test point")
      (footprint "Test_Point")
      (libsource (lib "hand_ad_lib") (part "Test_Point"))
    )
    (comp (ref "TP30")
      (value "Test point")
      (footprint "Test_Point")
      (libsource (lib "hand_ad_lib") (part "Test_Point"))
    )
    (comp (ref "TP31")
      (value "Test point")
      (footprint "Test_Point")
      (libsource (lib "hand_ad_lib") (part "Test_Point"))
    )
    (comp (ref "TP32")
      (value "Test point")
      (footprint "Test_Point")
      (libsource (lib "hand_ad_lib") (part "Test_Point"))
    )
    (comp (ref "TP33")
      (value "Test point")
      (footprint "Test_Point")
      (libsource (lib "hand_ad_lib") (part "Test_Point"))
    )
    (comp (ref "TP34")
      (value "Test point")
      (footprint "Test_Point")
      (libsource (lib "hand_ad_lib") (part "Test_Point"))
    )
    (comp (ref "TP35")
      (value "Test point")
      (footprint "Test_Point")
      (libsource (lib "hand_ad_lib") (part "Test_Point"))
    )
    (comp (ref "TP36")
      (value "Test point")
      (footprint "Test_Point")
      (libsource (lib "hand_ad_lib") (part "Test_Point"))
    )
    (comp (ref "TP37")
      (value "Test point")
      (footprint "Test_Point")
      (libsource (lib "hand_ad_lib") (part "Test_Point"))
    )
    (comp (ref "TP42")
      (value "Test point")
      (footprint "Test_Point")
      (libsource (lib "hand_ad_lib") (part "Test_Point"))
    )
    (comp (ref "TP43")
      (value "Test point")
      (footprint "Test_Point")
      (libsource (lib "hand_ad_lib") (part "Test_Point"))
    )
    (comp (ref "U23")
      (value "ESP32-S3-MINI-1-N8")
      (footprint "XCVR_ESP32-S3-MINI-1-N8")
      (description "Bluetooth, WiFi 802.11b/g/n, Bluetooth v5.0 Transceiver Module 2.4GHz PCB Trace Surface Mount")
      (fields (field (name "MF") "Espressif Systems"))
      (libsource (lib "hand_ad_lib") (part "ESP32-S3-MINI-1-N8"))
    )
    (comp (ref "U24")
      (value "TXB0104YZTR")
      (footprint "FP-YZT0012-IPC_B")
      (description "I2C Level Shifter 4 channel, IC TRNSLTR BIDIRECTIONAL 12DSBGA")
      (libsource (lib "hand_ad_lib") (part "TXB0104YZTR"))
    )
    (comp (ref "U25")
      (value "TXS0102DQER")
      (footprint "FP-DQE0008A-IPC_C")
      (fields
        (field (name "OCTOPART") "https://octopart.com/txs0102dqer-texas+instruments-19973770")
        (field (name "MANUFACTURER") "Texas Instruments")
      )
      (libsource (lib "hand_ad_lib") (part "TXS0102DQER"))
    )
    (comp (ref "U26")
      (value "TCA6408ARGTR")
      (footprint "RGT0016A_V")
      (fields (field (name "MANUFACTURER") "Texas Instruments"))
      (libsource (lib "hand_ad_lib") (part "TCA6408ARGTR"))
    )
    (comp (ref "U27")
      (value "TCA6408ARGTR")
      (footprint "RGT0016A_V")
      (fields (field (name "MANUFACTURER") "Texas Instruments"))
      (libsource (lib "hand_ad_lib") (part "TCA6408ARGTR"))
    )
    (comp (ref "U28")
      (value "BOS1901CWR")
      (footprint "BOS1901_BGA25C40P5X5_212X224X66")
      (libsource (lib "hand_ad_lib") (part "BOS1901CWR"))
    )
    (comp (ref "U29")
      (value "BOS1901CWR")
      (footprint "BOS1901_BGA25C40P5X5_212X224X66")
      (libsource (lib "hand_ad_lib") (part "BOS1901CWR"))
    )
    (comp (ref "U30")
      (value "BOS1901CWR")
      (footprint "BOS1901_BGA25C40P5X5_212X224X66")
      (libsource (lib "hand_ad_lib") (part "BOS1901CWR"))
    )
    (comp (ref "U31")
      (value "BOS1901CWR")
      (footprint "BOS1901_BGA25C40P5X5_212X224X66")
      (libsource (lib "hand_ad_lib") (part "BOS1901CWR"))
    )
    (comp (ref "X1")
      (value "32.768kHz")
      (footprint "OSC-SMD_4P-L2.5-W2.0-BL")
      (fields
        (field (name "MANUFACTURER") "YXC(扬兴晶振)")
        (field (name "MANUFACTURER PART") "OK252032.768KJBA4SL")
        (field (name "NAME") "32.768kHz")
      )
      (libsource (lib "hand_ad_lib") (part "OK252032.768KJBA4SL"))
    )
  )
  (nets
    (net (code "1") (name "+1.8V") (class "Default")
      (node (ref "C58") (pin "1") (pinfunction "1_1") (pintype "passive"))
      (node (ref "C59") (pin "1") (pinfunction "1_1") (pintype "passive"))
      (node (ref "C65") (pin "1") (pinfunction "1_1") (pintype "passive"))
      (node (ref "J4") (pin "19") (pinfunction "19_19") (pintype "passive"))
      (node (ref "J5") (pin "4") (pinfunction "4_4") (pintype "passive"))
      (node (ref "J5") (pin "42") (pinfunction "42_42") (pintype "passive"))
      (node (ref "R55") (pin "1") (pinfunction "1_1") (pintype "passive"))
      (node (ref "R56") (pin "2") (pinfunction "2_2") (pintype "passive"))
      (node (ref "R58") (pin "1") (pinfunction "1_1") (pintype "passive"))
      (node (ref "R59") (pin "2") (pinfunction "2_2") (pintype "passive"))
      (node (ref "U24") (pin "B2") (pinfunction "VCCA_B2") (pintype "power_in"))
      (node (ref "U24") (pin "C2") (pinfunction "OE_C2") (pintype "input"))
      (node (ref "U25") (pin "1") (pinfunction "VCCA_1") (pintype "power_in"))
      (node (ref "U25") (pin "5") (pinfunction "OE_5") (pintype "input"))
      (node (ref "U27") (pin "14") (pinfunction "VCCP_14") (pintype "power_in"))
    )
    (net (code "2") (name "+3.3V") (class "Default")
      (node (ref "C48") (pin "2") (pinfunction "2_2") (pintype "passive"))
      (node (ref "C51") (pin "2") (pinfunction "2_2") (pintype "passive"))
      (node (ref "C53") (pin "2") (pinfunction "2_2") (pintype "passive"))
      (node (ref "C54") (pin "2") (pinfunction "2_2") (pintype "passive"))
      (node (ref "C55") (pin "2") (pinfunction "2_2") (pintype "passive"))
      (node (ref "C56") (pin "2") (pinfunction "2_2") (pintype "passive"))
      (node (ref "C57") (pin "2") (pinfunction "2_2") (pintype "passive"))
      (node (ref "C60") (pin "1") (pinfunction "1_1") (pintype "passive"))
      (node (ref "C61") (pin "2") (pinfunction "2_2") (pintype "passive"))
      (node (ref "C62") (pin "1") (pinfunction "1_1") (pintype "passive"))
      (node (ref "C63") (pin "1") (pinfunction "1_1") (pintype "passive"))
      (node (ref "C64") (pin "1") (pinfunction "1_1") (pintype "passive"))
      (node (ref "C71") (pin "2") (pinfunction "2_2") (pintype "passive"))
      (node (ref "C72") (pin "2") (pinfunction "2_2") (pintype "passive"))
      (node (ref "C81") (pin "2") (pinfunction "2_2") (pintype "passive"))
      (node (ref "C82") (pin "2") (pinfunction "2_2") (pintype "passive"))
      (node (ref "J4") (pin "17") (pinfunction "17_17") (pintype "passive"))
      (node (ref "J5") (pin "3") (pinfunction "3_3") (pintype "passive"))
      (node (ref "J5") (pin "43") (pinfunction "43_43") (pintype "passive"))
      (node (ref "LED4") (pin "1") (pinfunction "VDD_1") (pintype "power_in"))
      (node (ref "R39") (pin "2") (pinfunction "2_2") (pintype "passive"))
      (node (ref "R42") (pin "2") (pinfunction "2_2") (pintype "passive"))
      (node (ref "R43") (pin "1") (pinfunction "1_1") (pintype "passive"))
      (node (ref "R48") (pin "2") (pinfunction "2_2") (pintype "passive"))
      (node (ref "R49") (pin "2") (pinfunction "2_2") (pintype "passive"))
      (node (ref "R60") (pin "1") (pinfunction "1_1") (pintype "passive"))
      (node (ref "R61") (pin "1") (pinfunction "1_1") (pintype "passive"))
      (node (ref "TP42") (pin "TP?") (pinfunction "Test_point_TP?") (pintype "passive"))
      (node (ref "U23") (pin "3") (pinfunction "3V3_3") (pintype "power_in"))
      (node (ref "U24") (pin "A2") (pinfunction "VCCB_A2") (pintype "power_in"))
      (node (ref "U25") (pin "8") (pinfunction "VCCB_8") (pintype "power_in"))
      (node (ref "U26") (pin "1") (pinfunction "~{RESET}_1") (pintype "input"))
      (node (ref "U26") (pin "14") (pinfunction "VCCP_14") (pintype "power_in"))
      (node (ref "U26") (pin "15") (pinfunction "VCCI_15") (pintype "power_in"))
      (node (ref "U27") (pin "1") (pinfunction "~{RESET}_1") (pintype "input"))
      (node (ref "U27") (pin "15") (pinfunction "VCCI_15") (pintype "power_in"))
      (node (ref "U27") (pin "16") (pinfunction "ADDR_16") (pintype "input"))
      (node (ref "U28") (pin "C4") (pinfunction "TST1_C4") (pintype "passive"))
      (node (ref "U28") (pin "D2") (pinfunction "TST2_D2") (pintype "passive"))
      (node (ref "U28") (pin "D3") (pinfunction "TST3_D3") (pintype "passive"))
      (node (ref "U28") (pin "E4") (pinfunction "VDDIO_E4") (pintype "power_in"))
      (node (ref "U29") (pin "C4") (pinfunction "TST1_C4") (pintype "passive"))
      (node (ref "U29") (pin "D2") (pinfunction "TST2_D2") (pintype "passive"))
      (node (ref "U29") (pin "D3") (pinfunction "TST3_D3") (pintype "passive"))
      (node (ref "U29") (pin "E4") (pinfunction "VDDIO_E4") (pintype "power_in"))
      (node (ref "U30") (pin "C4") (pinfunction "TST1_C4") (pintype "passive"))
      (node (ref "U30") (pin "D2") (pinfunction "TST2_D2") (pintype "passive"))
      (node (ref "U30") (pin "D3") (pinfunction "TST3_D3") (pintype "passive"))
      (node (ref "U30") (pin "E4") (pinfunction "VDDIO_E4") (pintype "power_in"))
      (node (ref "U31") (pin "C4") (pinfunction "TST1_C4") (pintype "passive"))
      (node (ref "U31") (pin "D2") (pinfunction "TST2_D2") (pintype "passive"))
      (node (ref "U31") (pin "D3") (pinfunction "TST3_D3") (pintype "passive"))
      (node (ref "U31") (pin "E4") (pinfunction "VDDIO_E4") (pintype "power_in"))
      (node (ref "X1") (pin "4") (pinfunction "VDD_4") (pintype "passive"))
    )
    (net (code "3") (name "+5V") (class "Default")
      (node (ref "U28") (pin "A2") (pinfunction "VBUS_A2") (pintype "power_in"))
      (node (ref "U29") (pin "A2") (pinfunction "VBUS_A2") (pintype "power_in"))
      (node (ref "U30") (pin "A2") (pinfunction "VBUS_A2") (pintype "power_in"))
      (node (ref "U31") (pin "A2") (pinfunction "VBUS_A2") (pintype "power_in"))
    )
    (net (code "4") (name "+VBUS") (class "Default")
      (node (ref "J4") (pin "18") (pinfunction "18_18") (pintype "passive"))
      (node (ref "R54") (pin "1") (pinfunction "1_1") (pintype "passive"))
    )
    (net (code "5") (name "/BAT_INSERT_DETECT") (class "Default")
      (node (ref "C66") (pin "2") (pinfunction "2_2") (pintype "passive"))
      (node (ref "R51") (pin "2") (pinfunction "2_2") (pintype "passive"))
      (node (ref "TP30") (pin "TP?") (pinfunction "Test_point_TP?") (pintype "passive"))
      (node (ref "U26") (pin "10") (pinfunction "P7_10") (pintype "bidirectional"))
    )
    (net (code "6") (name "/BOS1901_1_CS") (class "Default")
      (node (ref "U23") (pin "14") (pinfunction "IO10_14") (pintype "bidirectional"))
      (node (ref "U28") (pin "D4") (pinfunction "~{CS}_D4") (pintype "input"))
    )
    (net (code "7") (name "/BOS1901_2_CS") (class "Default")
      (node (ref "U23") (pin "13") (pinfunction "IO9_13") (pintype "bidirectional"))
      (node (ref "U30") (pin "D4") (pinfunction "~{CS}_D4") (pintype "input"))
    )
    (net (code "8") (name "/BOS1901_3_CS") (class "Default")
      (node (ref "U23") (pin "12") (pinfunction "IO8_12") (pintype "bidirectional"))
      (node (ref "U29") (pin "D4") (pinfunction "~{CS}_D4") (pintype "input"))
    )
    (net (code "9") (name "/BOS1901_4_CS") (class "Default")
      (node (ref "U23") (pin "11") (pinfunction "IO7_11") (pintype "bidirectional"))
      (node (ref "U31") (pin "D4") (pinfunction "~{CS}_D4") (pintype "input"))
    )
    (net (code "10") (name "/BQ25302_STAT") (class "Default")
      (node (ref "U26") (pin "4") (pinfunction "P2_4") (pintype "bidirectional"))
    )
    (net (code "11") (name "/BQ27427_GPOUT") (class "Default")
      (node (ref "U26") (pin "2") (pinfunction "P0_2") (pintype "bidirectional"))
    )
    (net (code "12") (name "/DEBUG_P1_TX") (class "Default")
      (node (ref "J4") (pin "11") (pinfunction "11_11") (pintype "passive"))
      (node (ref "R34") (pin "1") (pinfunction "1_1") (pintype "passive"))
      (node (ref "U23") (pin "39") (pinfunction "TXD0_39") (pintype "bidirectional"))
    )
    (net (code "13") (name "/DEBUG_P2_RX") (class "Default")
      (node (ref "J4") (pin "13") (pinfunction "13_13") (pintype "passive"))
      (node (ref "R35") (pin "1") (pinfunction "1_1") (pintype "passive"))
      (node (ref "U23") (pin "40") (pinfunction "RXD0_40") (pintype "bidirectional"))
    )
    (net (code "14") (name "/DEBUG_P3_RGB") (class "Default")
      (node (ref "J4") (pin "12") (pinfunction "12_12") (pintype "passive"))
      (node (ref "LED4") (pin "4") (pinfunction "DIN_4") (pintype "input"))
      (node (ref "R38") (pin "2") (pinfunction "2_2") (pintype "passive"))
      (node (ref "U23") (pin "41") (pinfunction "IO45_41") (pintype "bidirectional"))
    )
    (net (code "15") (name "/DEBUG_P4") (class "Default")
      (node (ref "J4") (pin "14") (pinfunction "14_14") (pintype "passive"))
      (node (ref "R37") (pin "2") (pinfunction "2_2") (pintype "passive"))
      (node (ref "U23") (pin "44") (pinfunction "IO46_44") (pintype "bidirectional"))
    )
    (net (code "16") (name "/ESP_CH101_SCL") (class "Default")
      (node (ref "U23") (pin "6") (pinfunction "IO2_6") (pintype "bidirectional"))
      (node (ref "U25") (pin "7") (pinfunction "B1_7") (pintype "bidirectional"))
    )
    (net (code "17") (name "/ESP_CH101_SDA") (class "Default")
      (node (ref "U23") (pin "7") (pinfunction "IO3_7") (pintype "bidirectional"))
      (node (ref "U25") (pin "6") (pinfunction "B2_6") (pintype "bidirectional"))
    )
    (net (code "18") (name "/ESP_EN") (class "Default")
      (node (ref "C49") (pin "1") (pinfunction "1_1") (pintype "passive"))
      (node (ref "J4") (pin "15") (pinfunction "15_15") (pintype "passive"))
      (node (ref "R40") (pin "2") (pinfunction "2_2") (pintype "passive"))
      (node (ref "R43") (pin "2") (pinfunction "2_2") (pintype "passive"))
      (node (ref "TP26") (pin "TP?") (pinfunction "Test_point_TP?") (pintype "passive"))
      (node (ref "U23") (pin "45") (pinfunction "EN_45") (pintype "input"))
    )
    (net (code "19") (name "/ESP_USB_N") (class "Default")
      (node (ref "R44") (pin "2") (pinfunction "2_2") (pintype "passive"))
    )
    (net (code "20") (name "/ESP_USB_P") (class "Default")
      (node (ref "R45") (pin "2") (pinfunction "2_2") (pintype "passive"))
    )
    (net (code "21") (name "/FPC_BMI323_CS") (class "Default")
      (node (ref "J5") (pin "23") (pinfunction "23_23") (pintype "passive"))
      (node (ref "U23") (pin "9") (pinfunction "IO5_9") (pintype "bidirectional"))
    )
    (net (code "22") (name "/FPC_BMI323_INT1") (class "Default")
      (node (ref "J5") (pin "22") (pinfunction "22_22") (pintype "passive"))
      (node (ref "U23") (pin "8") (pinfunction "IO4_8") (pintype "bidirectional"))
    )
    (net (code "23") (name "/FPC_BMI323_INT2") (class "Default")
      (node (ref "J5") (pin "24") (pinfunction "24_24") (pintype "passive"))
      (node (ref "R60") (pin "2") (pinfunction "2_2") (pintype "passive"))
      (node (ref "U26") (pin "7") (pinfunction "P4_7") (pintype "bidirectional"))
    )
    (net (code "24") (name "/FPC_BOARD_SCL") (class "Default")
      (node (ref "J4") (pin "7") (pinfunction "7_7") (pintype "passive"))
      (node (ref "J5") (pin "8") (pinfunction "8_8") (pintype "passive"))
      (node (ref "R42") (pin "1") (pinfunction "1_1") (pintype "passive"))
      (node (ref "SW5") (pin "2") (pinfunction "B_2") (pintype "passive"))
      (node (ref "TP25") (pin "TP?") (pinfunction "Test_point_TP?") (pintype "passive"))
      (node (ref "U23") (pin "4") (pinfunction "IO0_4") (pintype "bidirectional"))
      (node (ref "U26") (pin "12") (pinfunction "SCL_12") (pintype "input"))
      (node (ref "U27") (pin "12") (pinfunction "SCL_12") (pintype "input"))
    )
    (net (code "25") (name "/FPC_BOARD_SDA") (class "Default")
      (node (ref "J4") (pin "9") (pinfunction "9_9") (pintype "passive"))
      (node (ref "J5") (pin "9") (pinfunction "9_9") (pintype "passive"))
      (node (ref "R39") (pin "1") (pinfunction "1_1") (pintype "passive"))
      (node (ref "U23") (pin "5") (pinfunction "IO1_5") (pintype "bidirectional"))
      (node (ref "U26") (pin "13") (pinfunction "SDA_13") (pintype "bidirectional"))
      (node (ref "U27") (pin "13") (pinfunction "SDA_13") (pintype "bidirectional"))
    )
    (net (code "26") (name "/FPC_BOS1901_1_OUT+") (class "Default")
      (node (ref "J3") (pin "16") (pinfunction "16_16") (pintype "passive"))
      (node (ref "J3") (pin "17") (pinfunction "17_17") (pintype "passive"))
      (node (ref "J3") (pin "18") (pinfunction "18_18") (pintype "passive"))
      (node (ref "TP34") (pin "TP?") (pinfunction "Test_point_TP?") (pintype "passive"))
      (node (ref "U28") (pin "B1") (pinfunction "OUT+_B1") (pintype "output"))
    )
    (net (code "27") (name "/FPC_BOS1901_1_OUT−") (class "Default")
      (node (ref "J3") (pin "13") (pinfunction "13_13") (pintype "passive"))
      (node (ref "J3") (pin "14") (pinfunction "14_14") (pintype "passive"))
      (node (ref "J3") (pin "15") (pinfunction "15_15") (pintype "passive"))
      (node (ref "TP35") (pin "TP?") (pinfunction "Test_point_TP?") (pintype "passive"))
      (node (ref "U28") (pin "C1") (pinfunction "OUT−_C1") (pintype "output"))
    )
    (net (code "28") (name "/FPC_BOS1901_2_OUT+") (class "Default")
      (node (ref "J3") (pin "22") (pinfunction "22_22") (pintype "passive"))
      (node (ref "J3") (pin "23") (pinfunction "23_23") (pintype "passive"))
      (node (ref "J3") (pin "24") (pinfunction "24_24") (pintype "passive"))
      (node (ref "U30") (pin "B1") (pinfunction "OUT+_B1") (pintype "output"))
    )
    (net (code "29") (name "/FPC_BOS1901_2_OUT−") (class "Default")
      (node (ref "J3") (pin "19") (pinfunction "19_19") (pintype "passive"))
      (node (ref "J3") (pin "20") (pinfunction "20_20") (pintype "passive"))
      (node (ref "J3") (pin "21") (pinfunction "21_21") (pintype "passive"))
      (node (ref "U30") (pin "C1") (pinfunction "OUT−_C1") (pintype "output"))
    )
    (net (code "30") (name "/FPC_BOS1901_3_OUT+") (class "Default")
      (node (ref "J3") (pin "1") (pinfunction "1_1") (pintype "passive"))
      (node (ref "J3") (pin "2") (pinfunction "2_2") (pintype "passive"))
      (node (ref "J3") (pin "3") (pinfunction "3_3") (pintype "passive"))
      (node (ref "U29") (pin "B1") (pinfunction "OUT+_B1") (pintype "output"))
    )
    (net (code "31") (name "/FPC_BOS1901_3_OUT−") (class "Default")
      (node (ref "J3") (pin "4") (pinfunction "4_4") (pintype "passive"))
      (node (ref "J3") (pin "5") (pinfunction "5_5") (pintype "passive"))
      (node (ref "J3") (pin "6") (pinfunction "6_6") (pintype "passive"))
      (node (ref "U29") (pin "C1") (pinfunction "OUT−_C1") (pintype "output"))
    )
    (net (code "32") (name "/FPC_BOS1901_4_OUT+") (class "Default")
      (node (ref "J3") (pin "7") (pinfunction "7_7") (pintype "passive"))
      (node (ref "J3") (pin "8") (pinfunction "8_8") (pintype "passive"))
      (node (ref "J3") (pin "9") (pinfunction "9_9") (pintype "passive"))
      (node (ref "U31") (pin "B1") (pinfunction "OUT+_B1") (pintype "output"))
    )
    (net (code "33") (name "/FPC_BOS1901_4_OUT−") (class "Default")
      (node (ref "J3") (pin "10") (pinfunction "10_10") (pintype "passive"))
      (node (ref "J3") (pin "11") (pinfunction "11_11") (pintype "passive"))
      (node (ref "J3") (pin "12") (pinfunction "12_12") (pintype "passive"))
      (node (ref "U31") (pin "C1") (pinfunction "OUT−_C1") (pintype "output"))
    )
    (net (code "34") (name "/FPC_CH101_1_INT") (class "Default")
      (node (ref "J5") (pin "30") (pinfunction "30_30") (pintype "passive"))
      (node (ref "U24") (pin "A3") (pinfunction "A1_A3") (pintype "bidirectional"))
    )
    (net (code "35") (name "/FPC_CH101_1_PROG") (class "Default")
      (node (ref "J5") (pin "32") (pinfunction "32_32") (pintype "passive"))
      (node (ref "U27") (pin "2") (pinfunction "P0_2") (pintype "bidirectional"))
    )
    (net (code "36") (name "/FPC_CH101_1_RESET") (class "Default")
      (node (ref "J5") (pin "31") (pinfunction "31_31") (pintype "passive"))
      (node (ref "R58") (pin "2") (pinfunction "2_2") (pintype "passive"))
      (node (ref "TP28") (pin "TP?") (pinfunction "Test_point_TP?") (pintype "passive"))
      (node (ref "U27") (pin "3") (pinfunction "P1_3") (pintype "bidirectional"))
    )
    (net (code "37") (name "/FPC_CH101_2_INT") (class "Default")
      (node (ref "J5") (pin "27") (pinfunction "27_27") (pintype "passive"))
      (node (ref "U24") (pin "B3") (pinfunction "A2_B3") (pintype "bidirectional"))
    )
    (net (code "38") (name "/FPC_CH101_2_PROG") (class "Default")
      (node (ref "J5") (pin "29") (pinfunction "29_29") (pintype "passive"))
      (node (ref "U27") (pin "4") (pinfunction "P2_4") (pintype "bidirectional"))
    )
    (net (code "39") (name "/FPC_CH101_2_RESET") (class "Default")
      (node (ref "J5") (pin "28") (pinfunction "28_28") (pintype "passive"))
      (node (ref "R55") (pin "2") (pinfunction "2_2") (pintype "passive"))
      (node (ref "U27") (pin "5") (pinfunction "P3_5") (pintype "bidirectional"))
    )
    (net (code "40") (name "/FPC_CH101_3_INT") (class "Default")
      (node (ref "J5") (pin "19") (pinfunction "19_19") (pintype "passive"))
      (node (ref "U24") (pin "C3") (pinfunction "A3_C3") (pintype "bidirectional"))
    )
    (net (code "41") (name "/FPC_CH101_3_PROG") (class "Default")
      (node (ref "J5") (pin "17") (pinfunction "17_17") (pintype "passive"))
      (node (ref "U27") (pin "7") (pinfunction "P4_7") (pintype "bidirectional"))
    )
    (net (code "42") (name "/FPC_CH101_3_RESET") (class "Default")
      (node (ref "J5") (pin "18") (pinfunction "18_18") (pintype "passive"))
      (node (ref "R56") (pin "1") (pinfunction "1_1") (pintype "passive"))
      (node (ref "U27") (pin "8") (pinfunction "P5_8") (pintype "bidirectional"))
    )
    (net (code "43") (name "/FPC_CH101_4_INT") (class "Default")
      (node (ref "J5") (pin "16") (pinfunction "16_16") (pintype "passive"))
      (node (ref "U24") (pin "D3") (pinfunction "A4_D3") (pintype "bidirectional"))
    )
    (net (code "44") (name "/FPC_CH101_4_PROG") (class "Default")
      (node (ref "J5") (pin "14") (pinfunction "14_14") (pintype "passive"))
      (node (ref "U27") (pin "9") (pinfunction "P6_9") (pintype "bidirectional"))
    )
    (net (code "45") (name "/FPC_CH101_4_RESET") (class "Default")
      (node (ref "J5") (pin "15") (pinfunction "15_15") (pintype "passive"))
      (node (ref "R59") (pin "1") (pinfunction "1_1") (pintype "passive"))
      (node (ref "U27") (pin "10") (pinfunction "P7_10") (pintype "bidirectional"))
    )
    (net (code "46") (name "/FPC_CH101_SCL") (class "Default")
      (node (ref "J4") (pin "8") (pinfunction "8_8") (pintype "passive"))
      (node (ref "J5") (pin "38") (pinfunction "38_38") (pintype "passive"))
      (node (ref "U25") (pin "2") (pinfunction "A1_2") (pintype "bidirectional"))
    )
    (net (code "47") (name "/FPC_CH101_SDA") (class "Default")
      (node (ref "J4") (pin "10") (pinfunction "10_10") (pintype "passive"))
      (node (ref "J5") (pin "37") (pinfunction "37_37") (pintype "passive"))
      (node (ref "U25") (pin "3") (pinfunction "A2_3") (pintype "bidirectional"))
    )
    (net (code "48") (name "/FPC_KX132_1_CS") (class "Default")
      (node (ref "J5") (pin "36") (pinfunction "36_36") (pintype "passive"))
      (node (ref "U23") (pin "10") (pinfunction "IO6_10") (pintype "bidirectional"))
    )
    (net (code "49") (name "/FPC_KX132_1_INT1") (class "Default")
      (node (ref "J5") (pin "35") (pinfunction "35_35") (pintype "passive"))
      (node (ref "U23") (pin "29") (pinfunction "IO34_29") (pintype "bidirectional"))
    )
    (net (code "50") (name "/FPC_KX132_2_CS") (class "Default")
      (node (ref "J5") (pin "34") (pinfunction "34_34") (pintype "passive"))
      (node (ref "U23") (pin "35") (pinfunction "IO39_35") (pintype "bidirectional"))
    )
    (net (code "51") (name "/FPC_KX132_2_INT1") (class "Default")
      (node (ref "J5") (pin "33") (pinfunction "33_33") (pintype "passive"))
      (node (ref "U23") (pin "34") (pinfunction "IO38_34") (pintype "bidirectional"))
    )
    (net (code "52") (name "/FPC_KX132_3_CS") (class "Default")
      (node (ref "J5") (pin "12") (pinfunction "12_12") (pintype "passive"))
      (node (ref "U23") (pin "33") (pinfunction "IO37_33") (pintype "bidirectional"))
    )
    (net (code "53") (name "/FPC_KX132_3_INT1") (class "Default")
      (node (ref "J5") (pin "13") (pinfunction "13_13") (pintype "passive"))
      (node (ref "U23") (pin "32") (pinfunction "IO36_32") (pintype "bidirectional"))
    )
    (net (code "54") (name "/FPC_KX132_4_CS") (class "Default")
      (node (ref "J5") (pin "10") (pinfunction "10_10") (pintype "passive"))
      (node (ref "U23") (pin "31") (pinfunction "IO35_31") (pintype "bidirectional"))
    )
    (net (code "55") (name "/FPC_KX132_4_INT1") (class "Default")
      (node (ref "J5") (pin "11") (pinfunction "11_11") (pintype "passive"))
      (node (ref "U23") (pin "30") (pinfunction "IO48_30") (pintype "bidirectional"))
    )
    (net (code "56") (name "/FPC_SPI2_SCLK") (class "Default")
      (node (ref "J4") (pin "3") (pinfunction "3_3") (pintype "passive"))
      (node (ref "J5") (pin "6") (pinfunction "6_6") (pintype "passive"))
      (node (ref "R41") (pin "1") (pinfunction "1_1") (pintype "passive"))
      (node (ref "U28") (pin "E5") (pinfunction "SCLK_E5") (pintype "input"))
      (node (ref "U29") (pin "E5") (pinfunction "SCLK_E5") (pintype "input"))
      (node (ref "U30") (pin "E5") (pinfunction "SCLK_E5") (pintype "input"))
      (node (ref "U31") (pin "E5") (pinfunction "SCLK_E5") (pintype "input"))
    )
    (net (code "57") (name "/FPC_SPI2_SDI") (class "Default")
      (node (ref "J4") (pin "5") (pinfunction "5_5") (pintype "passive"))
      (node (ref "J5") (pin "5") (pinfunction "5_5") (pintype "passive"))
      (node (ref "R36") (pin "1") (pinfunction "1_1") (pintype "passive"))
      (node (ref "U28") (pin "D5") (pinfunction "SDI_D5") (pintype "input"))
      (node (ref "U29") (pin "D5") (pinfunction "SDI_D5") (pintype "input"))
      (node (ref "U30") (pin "D5") (pinfunction "SDI_D5") (pintype "input"))
      (node (ref "U31") (pin "D5") (pinfunction "SDI_D5") (pintype "input"))
    )
    (net (code "58") (name "/FPC_SPI2_SDO") (class "Default")
      (node (ref "J4") (pin "1") (pinfunction "1_1") (pintype "passive"))
      (node (ref "J5") (pin "7") (pinfunction "7_7") (pintype "passive"))
      (node (ref "R62") (pin "1") (pinfunction "1_1") (pintype "passive"))
      (node (ref "R63") (pin "1") (pinfunction "1_1") (pintype "passive"))
      (node (ref "R66") (pin "1") (pinfunction "1_1") (pintype "passive"))
      (node (ref "R67") (pin "1") (pinfunction "1_1") (pintype "passive"))
      (node (ref "U23") (pin "15") (pinfunction "IO11_15") (pintype "bidirectional"))
    )
    (net (code "59") (name "/FPC_SPI3_SCLK") (class "Default")
      (node (ref "J4") (pin "4") (pinfunction "4_4") (pintype "passive"))
      (node (ref "J5") (pin "40") (pinfunction "40_40") (pintype "passive"))
      (node (ref "R46") (pin "2") (pinfunction "2_2") (pintype "passive"))
    )
    (net (code "60") (name "/FPC_SPI3_SDI") (class "Default")
      (node (ref "J4") (pin "6") (pinfunction "6_6") (pintype "passive"))
      (node (ref "J5") (pin "41") (pinfunction "41_41") (pintype "passive"))
      (node (ref "R47") (pin "2") (pinfunction "2_2") (pintype "passive"))
    )
    (net (code "61") (name "/FPC_SPI3_SDO") (class "Default")
      (node (ref "J4") (pin "2") (pinfunction "2_2") (pintype "passive"))
      (node (ref "J5") (pin "39") (pinfunction "39_39") (pintype "passive"))
      (node (ref "U23") (pin "36") (pinfunction "IO40_36") (pintype "bidirectional"))
    )
    (net (code "62") (name "/FPC_VL53L1X_1_GPIO1") (class "Default")
      (node (ref "J5") (pin "26") (pinfunction "26_26") (pintype "passive"))
      (node (ref "U23") (pin "21") (pinfunction "IO17_21") (pintype "bidirectional"))
    )
    (net (code "63") (name "/FPC_VL53L1X_1_XSHUT") (class "Default")
      (node (ref "J5") (pin "25") (pinfunction "25_25") (pintype "passive"))
      (node (ref "R61") (pin "2") (pinfunction "2_2") (pintype "passive"))
      (node (ref "TP31") (pin "TP?") (pinfunction "Test_point_TP?") (pintype "passive"))
      (node (ref "U26") (pin "5") (pinfunction "P3_5") (pintype "bidirectional"))
    )
    (net (code "64") (name "/FPC_VL53L1X_2_GPIO1") (class "Default")
      (node (ref "J5") (pin "20") (pinfunction "20_20") (pintype "passive"))
      (node (ref "U23") (pin "22") (pinfunction "IO18_22") (pintype "bidirectional"))
    )
    (net (code "65") (name "/FPC_VL53L1X_2_XSHUT") (class "Default")
      (node (ref "J5") (pin "21") (pinfunction "21_21") (pintype "passive"))
      (node (ref "R57") (pin "2") (pinfunction "2_2") (pintype "passive"))
      (node (ref "TP29") (pin "TP?") (pinfunction "Test_point_TP?") (pintype "passive"))
      (node (ref "U26") (pin "8") (pinfunction "P5_8") (pintype "bidirectional"))
    )
    (net (code "66") (name "/TCA_BQ25302_EN") (class "Default")
      (node (ref "U26") (pin "3") (pinfunction "P1_3") (pintype "bidirectional"))
    )
    (net (code "67") (name "/TCA_INT") (class "Default")
      (node (ref "R48") (pin "1") (pinfunction "1_1") (pintype "passive"))
      (node (ref "TP27") (pin "TP?") (pinfunction "Test_point_TP?") (pintype "passive"))
      (node (ref "U23") (pin "18") (pinfunction "IO14_18") (pintype "bidirectional"))
      (node (ref "U26") (pin "11") (pinfunction "~{INT}_11") (pintype "open_collector"))
    )
    (net (code "68") (name "/TXB0104_B1") (class "Default")
      (node (ref "U23") (pin "28") (pinfunction "IO33_28") (pintype "bidirectional"))
      (node (ref "U24") (pin "A1") (pinfunction "B1_A1") (pintype "bidirectional"))
    )
    (net (code "69") (name "/TXB0104_B2") (class "Default")
      (node (ref "U23") (pin "27") (pinfunction "IO47_27") (pintype "bidirectional"))
      (node (ref "U24") (pin "B1") (pinfunction "B2_B1") (pintype "bidirectional"))
    )
    (net (code "70") (name "/TXB0104_B3") (class "Default")
      (node (ref "U23") (pin "26") (pinfunction "IO26_26") (pintype "bidirectional"))
      (node (ref "U24") (pin "C1") (pinfunction "B3_C1") (pintype "bidirectional"))
    )
    (net (code "71") (name "/TXB0104_B4") (class "Default")
      (node (ref "U23") (pin "25") (pinfunction "IO21_25") (pintype "bidirectional"))
      (node (ref "U24") (pin "D1") (pinfunction "B4_D1") (pintype "bidirectional"))
    )
    (net (code "72") (name "/USB_RES_N") (class "Default")
      (node (ref "R44") (pin "1") (pinfunction "1_1") (pintype "passive"))
      (node (ref "U23") (pin "23") (pinfunction "IO19_23") (pintype "bidirectional"))
    )
    (net (code "73") (name "/USB_RES_P") (class "Default")
      (node (ref "R45") (pin "1") (pinfunction "1_1") (pintype "passive"))
      (node (ref "U23") (pin "24") (pinfunction "IO20_24") (pintype "bidirectional"))
    )
    (net (code "74") (name "/VBUS_INSERT_DETECT") (class "Default")
      (node (ref "R54") (pin "2") (pinfunction "2_2") (pintype "passive"))
      (node (ref "U26") (pin "9") (pinfunction "P6_9") (pintype "bidirectional"))
    )
    (net (code "75") (name "BAT+") (class "Default")
      (node (ref "J4") (pin "16") (pinfunction "16_16") (pintype "passive"))
      (node (ref "R50") (pin "2") (pinfunction "2_2") (pintype "passive"))
      (node (ref "R51") (pin "1") (pinfunction "1_1") (pintype "passive"))
    )
    (net (code "76") (name "GND") (class "Default")
      (node (ref "C48") (pin "1") (pinfunction "1_1") (pintype "passive"))
      (node (ref "C49") (pin "2") (pinfunction "2_2") (pintype "passive"))
      (node (ref "C50") (pin "2") (pinfunction "2_2") (pintype "passive"))
      (node (ref "C51") (pin "1") (pinfunction "1_1") (pintype "passive"))
      (node (ref "C53") (pin "1") (pinfunction "1_1") (pintype "passive"))
      (node (ref "C54") (pin "1") (pinfunction "1_1") (pintype "passive"))
      (node (ref "C55") (pin "1") (pinfunction "1_1") (pintype "passive"))
      (node (ref "C56") (pin "1") (pinfunction "1_1") (pintype "passive"))
      (node (ref "C57") (pin "1") (pinfunction "1_1") (pintype "passive"))
      (node (ref "C58") (pin "2") (pinfunction "2_2") (pintype "passive"))
      (node (ref "C59") (pin "2") (pinfunction "2_2") (pintype "passive"))
      (node (ref "C60") (pin "2") (pinfunction "2_2") (pintype "passive"))
      (node (ref "C61") (pin "1") (pinfunction "1_1") (pintype "passive"))
      (node (ref "C62") (pin "2") (pinfunction "2_2") (pintype "passive"))
      (node (ref "C63") (pin "2") (pinfunction "2_2") (pintype "passive"))
      (node (ref "C64") (pin "2") (pinfunction "2_2") (pintype "passive"))
      (node (ref "C65") (pin "2") (pinfunction "2_2") (pintype "passive"))
      (node (ref "C66") (pin "1") (pinfunction "1_1") (pintype "passive"))
      (node (ref "C67") (pin "2") (pinfunction "2_2") (pintype "passive"))
      (node (ref "C68") (pin "2") (pinfunction "2_2") (pintype "passive"))
      (node (ref "C69") (pin "1") (pinfunction "1_1") (pintype "passive"))
      (node (ref "C70") (pin "1") (pinfunction "1_1") (pintype "passive"))
      (node (ref "C71") (pin "1") (pinfunction "1_1") (pintype "passive"))
      (node (ref "C72") (pin "1") (pinfunction "1_1") (pintype "passive"))
      (node (ref "C75") (pin "1") (pinfunction "1_1") (pintype "passive"))
      (node (ref "C76") (pin "1") (pinfunction "1_1") (pintype "passive"))
      (node (ref "C77") (pin "2") (pinfunction "2_2") (pintype "passive"))
      (node (ref "C78") (pin "2") (pinfunction "2_2") (pintype "passive"))
      (node (ref "C79") (pin "1") (pinfunction "1_1") (pintype "passive"))
      (node (ref "C80") (pin "1") (pinfunction "1_1") (pintype "passive"))
      (node (ref "C81") (pin "1") (pinfunction "1_1") (pintype "passive"))
      (node (ref "C82") (pin "1") (pinfunction "1_1") (pintype "passive"))
      (node (ref "C85") (pin "1") (pinfunction "1_1") (pintype "passive"))
      (node (ref "C86") (pin "1") (pinfunction "1_1") (pintype "passive"))
      (node (ref "D1") (pin "2") (pinfunction "A_2") (pintype "passive"))
      (node (ref "D2") (pin "2") (pinfunction "A_2") (pintype "passive"))
      (node (ref "D3") (pin "2") (pinfunction "A_2") (pintype "passive"))
      (node (ref "D4") (pin "2") (pinfunction "A_2") (pintype "passive"))
      (node (ref "J4") (pin "20") (pinfunction "20_20") (pintype "passive"))
      (node (ref "J5") (pin "1") (pinfunction "1_1") (pintype "passive"))
      (node (ref "J5") (pin "2") (pinfunction "2_2") (pintype "passive"))
      (node (ref "J5") (pin "44") (pinfunction "44_44") (pintype "passive"))
      (node (ref "J5") (pin "45") (pinfunction "45_45") (pintype "passive"))
      (node (ref "LED4") (pin "3") (pinfunction "VSS_3") (pintype "power_in"))
      (node (ref "LED5") (pin "1") (pinfunction "K_1") (pintype "passive"))
      (node (ref "LED6") (pin "2") (pinfunction "K_2") (pintype "passive"))
      (node (ref "R37") (pin "1") (pinfunction "1_1") (pintype "passive"))
      (node (ref "R38") (pin "1") (pinfunction "1_1") (pintype "passive"))
      (node (ref "R50") (pin "1") (pinfunction "1_1") (pintype "passive"))
      (node (ref "R57") (pin "1") (pinfunction "1_1") (pintype "passive"))
      (node (ref "SW4") (pin "3") (pinfunction "C_3") (pintype "passive"))
      (node (ref "SW5") (pin "3") (pinfunction "C_3") (pintype "passive"))
      (node (ref "TP43") (pin "TP?") (pinfunction "Test_point_TP?") (pintype "passive"))
      (node (ref "U23") (pin "1") (pinfunction "GND_1") (pintype "power_in"))
      (node (ref "U23") (pin "2") (pinfunction "GND_2") (pintype "power_in"))
      (node (ref "U23") (pin "42") (pinfunction "GND_42") (pintype "power_in"))
      (node (ref "U23") (pin "43") (pinfunction "GND_43") (pintype "power_in"))
      (node (ref "U23") (pin "46") (pinfunction "GND_46") (pintype "power_in"))
      (node (ref "U23") (pin "47") (pinfunction "GND_47") (pintype "power_in"))
      (node (ref "U23") (pin "48") (pinfunction "GND_48") (pintype "power_in"))
      (node (ref "U23") (pin "49") (pinfunction "GND_49") (pintype "power_in"))
      (node (ref "U23") (pin "50") (pinfunction "GND_50") (pintype "power_in"))
      (node (ref "U23") (pin "51") (pinfunction "GND_51") (pintype "power_in"))
      (node (ref "U23") (pin "52") (pinfunction "GND_52") (pintype "power_in"))
      (node (ref "U23") (pin "53") (pinfunction "GND_53") (pintype "power_in"))
      (node (ref "U23") (pin "54") (pinfunction "GND_54") (pintype "power_in"))
      (node (ref "U23") (pin "55") (pinfunction "GND_55") (pintype "power_in"))
      (node (ref "U23") (pin "56") (pinfunction "GND_56") (pintype "power_in"))
      (node (ref "U23") (pin "57") (pinfunction "GND_57") (pintype "power_in"))
      (node (ref "U23") (pin "58") (pinfunction "GND_58") (pintype "power_in"))
      (node (ref "U23") (pin "59") (pinfunction "GND_59") (pintype "power_in"))
      (node (ref "U23") (pin "60") (pinfunction "GND_60") (pintype "power_in"))
      (node (ref "U23") (pin "61") (pinfunction "GND_61") (pintype "power_in"))
      (node (ref "U23") (pin "61_1") (pinfunction "GND_61_1") (pintype "power_in"))
      (node (ref "U23") (pin "61_2") (pinfunction "GND_61_2") (pintype "power_in"))
      (node (ref "U23") (pin "61_3") (pinfunction "GND_61_3") (pintype "power_in"))
      (node (ref "U23") (pin "61_4") (pinfunction "GND_61_4") (pintype "power_in"))
      (node (ref "U23") (pin "61_5") (pinfunction "GND_61_5") (pintype "power_in"))
      (node (ref "U23") (pin "61_6") (pinfunction "GND_61_6") (pintype "power_in"))
      (node (ref "U23") (pin "61_7") (pinfunction "GND_61_7") (pintype "power_in"))
      (node (ref "U23") (pin "61_8") (pinfunction "GND_61_8") (pintype "power_in"))
      (node (ref "U23") (pin "62") (pinfunction "GND_62") (pintype "power_in"))
      (node (ref "U23") (pin "63") (pinfunction "GND_63") (pintype "power_in"))
      (node (ref "U23") (pin "64") (pinfunction "GND_64") (pintype "power_in"))
      (node (ref "U23") (pin "65") (pinfunction "GND_65") (pintype "power_in"))
      (node (ref "U24") (pin "D2") (pinfunction "GND_D2") (pintype "power_in"))
      (node (ref "U25") (pin "4") (pinfunction "GND_4") (pintype "power_in"))
      (node (ref "U26") (pin "16") (pinfunction "ADDR_16") (pintype "input"))
      (node (ref "U26") (pin "17") (pinfunction "EP_17") (pintype "passive"))
      (node (ref "U26") (pin "6") (pinfunction "GND_6") (pintype "power_in"))
      (node (ref "U27") (pin "17") (pinfunction "EP_17") (pintype "passive"))
      (node (ref "U27") (pin "6") (pinfunction "GND_6") (pintype "power_in"))
      (node (ref "U28") (pin "A5") (pinfunction "GND_A5") (pintype "power_in"))
      (node (ref "U28") (pin "B2") (pinfunction "GND_B2") (pintype "power_in"))
      (node (ref "U28") (pin "E1") (pinfunction "GND_E1") (pintype "power_in"))
      (node (ref "U29") (pin "A5") (pinfunction "GND_A5") (pintype "power_in"))
      (node (ref "U29") (pin "B2") (pinfunction "GND_B2") (pintype "power_in"))
      (node (ref "U29") (pin "E1") (pinfunction "GND_E1") (pintype "power_in"))
      (node (ref "U30") (pin "A5") (pinfunction "GND_A5") (pintype "power_in"))
      (node (ref "U30") (pin "B2") (pinfunction "GND_B2") (pintype "power_in"))
      (node (ref "U30") (pin "E1") (pinfunction "GND_E1") (pintype "power_in"))
      (node (ref "U31") (pin "A5") (pinfunction "GND_A5") (pintype "power_in"))
      (node (ref "U31") (pin "B2") (pinfunction "GND_B2") (pintype "power_in"))
      (node (ref "U31") (pin "E1") (pinfunction "GND_E1") (pintype "power_in"))
      (node (ref "X1") (pin "2") (pinfunction "GND_2") (pintype "passive"))
    )
    (net (code "77") (name "Net-(D1-K)") (class "Default")
      (node (ref "C67") (pin "1") (pinfunction "1_1") (pintype "passive"))
      (node (ref "C74") (pin "2") (pinfunction "2_2") (pintype "passive"))
      (node (ref "D1") (pin "1") (pinfunction "K_1") (pintype "passive"))
      (node (ref "R65") (pin "1") (pinfunction "1_1") (pintype "passive"))
      (node (ref "TP32") (pin "TP?") (pinfunction "Test_point_TP?") (pintype "passive"))
      (node (ref "U29") (pin "A1") (pinfunction "VDD_A1") (pintype "power_in"))
      (node (ref "U29") (pin "B3") (pinfunction "RP_B3") (pintype "input"))
    )
    (net (code "78") (name "Net-(D2-K)") (class "Default")
      (node (ref "C68") (pin "1") (pinfunction "1_1") (pintype "passive"))
      (node (ref "C73") (pin "2") (pinfunction "2_2") (pintype "passive"))
      (node (ref "D2") (pin "1") (pinfunction "K_1") (pintype "passive"))
      (node (ref "R64") (pin "1") (pinfunction "1_1") (pintype "passive"))
      (node (ref "TP33") (pin "TP?") (pinfunction "Test_point_TP?") (pintype "passive"))
      (node (ref "U28") (pin "A1") (pinfunction "VDD_A1") (pintype "power_in"))
      (node (ref "U28") (pin "B3") (pinfunction "RP_B3") (pintype "input"))
    )
    (net (code "79") (name "Net-(D3-K)") (class "Default")
      (node (ref "C77") (pin "1") (pinfunction "1_1") (pintype "passive"))
      (node (ref "C83") (pin "2") (pinfunction "2_2") (pintype "passive"))
      (node (ref "D3") (pin "1") (pinfunction "K_1") (pintype "passive"))
      (node (ref "R68") (pin "1") (pinfunction "1_1") (pintype "passive"))
      (node (ref "TP36") (pin "TP?") (pinfunction "Test_point_TP?") (pintype "passive"))
      (node (ref "U30") (pin "A1") (pinfunction "VDD_A1") (pintype "power_in"))
      (node (ref "U30") (pin "B3") (pinfunction "RP_B3") (pintype "input"))
    )
    (net (code "80") (name "Net-(D4-K)") (class "Default")
      (node (ref "C78") (pin "1") (pinfunction "1_1") (pintype "passive"))
      (node (ref "C84") (pin "2") (pinfunction "2_2") (pintype "passive"))
      (node (ref "D4") (pin "1") (pinfunction "K_1") (pintype "passive"))
      (node (ref "R69") (pin "1") (pinfunction "1_1") (pintype "passive"))
      (node (ref "TP37") (pin "TP?") (pinfunction "Test_point_TP?") (pintype "passive"))
      (node (ref "U31") (pin "A1") (pinfunction "VDD_A1") (pintype "power_in"))
      (node (ref "U31") (pin "B3") (pinfunction "RP_B3") (pintype "input"))
    )
    (net (code "81") (name "Net-(L4-Pad2)") (class "Default")
      (node (ref "L4") (pin "2") (pinfunction "2_2") (pintype "passive"))
      (node (ref "U28") (pin "E2") (pinfunction "SW_E2") (pintype "power_in"))
      (node (ref "U28") (pin "E3") (pinfunction "SW_E3") (pintype "power_in"))
    )
    (net (code "82") (name "Net-(L5-Pad2)") (class "Default")
      (node (ref "L5") (pin "2") (pinfunction "2_2") (pintype "passive"))
      (node (ref "U29") (pin "E2") (pinfunction "SW_E2") (pintype "power_in"))
      (node (ref "U29") (pin "E3") (pinfunction "SW_E3") (pintype "power_in"))
    )
    (net (code "83") (name "Net-(L6-Pad2)") (class "Default")
      (node (ref "L6") (pin "2") (pinfunction "2_2") (pintype "passive"))
      (node (ref "U30") (pin "E2") (pinfunction "SW_E2") (pintype "power_in"))
      (node (ref "U30") (pin "E3") (pinfunction "SW_E3") (pintype "power_in"))
    )
    (net (code "84") (name "Net-(L7-Pad2)") (class "Default")
      (node (ref "L7") (pin "2") (pinfunction "2_2") (pintype "passive"))
      (node (ref "U31") (pin "E2") (pinfunction "SW_E2") (pintype "power_in"))
      (node (ref "U31") (pin "E3") (pinfunction "SW_E3") (pintype "power_in"))
    )
    (net (code "85") (name "Net-(LED5-A)") (class "Default")
      (node (ref "LED5") (pin "2") (pinfunction "A_2") (pintype "passive"))
      (node (ref "R34") (pin "2") (pinfunction "2_2") (pintype "passive"))
    )
    (net (code "86") (name "Net-(LED6-A)") (class "Default")
      (node (ref "LED6") (pin "1") (pinfunction "A_1") (pintype "passive"))
      (node (ref "R35") (pin "2") (pinfunction "2_2") (pintype "passive"))
    )
    (net (code "87") (name "Net-(SW4-B)") (class "Default")
      (node (ref "C50") (pin "1") (pinfunction "1_1") (pintype "passive"))
      (node (ref "R40") (pin "1") (pinfunction "1_1") (pintype "passive"))
      (node (ref "SW4") (pin "2") (pinfunction "B_2") (pintype "passive"))
    )
    (net (code "88") (name "Net-(U23-IO12)") (class "Default")
      (node (ref "R41") (pin "2") (pinfunction "2_2") (pintype "passive"))
      (node (ref "U23") (pin "16") (pinfunction "IO12_16") (pintype "bidirectional"))
    )
    (net (code "89") (name "Net-(U23-IO13)") (class "Default")
      (node (ref "R36") (pin "2") (pinfunction "2_2") (pintype "passive"))
      (node (ref "U23") (pin "17") (pinfunction "IO13_17") (pintype "bidirectional"))
    )
    (net (code "90") (name "Net-(U23-IO15)") (class "Default")
      (node (ref "C52") (pin "2") (pinfunction "2_2") (pintype "passive"))
      (node (ref "U23") (pin "19") (pinfunction "IO15_19") (pintype "bidirectional"))
    )
    (net (code "91") (name "Net-(U23-IO41)") (class "Default")
      (node (ref "R46") (pin "1") (pinfunction "1_1") (pintype "passive"))
      (node (ref "U23") (pin "37") (pinfunction "IO41_37") (pintype "bidirectional"))
    )
    (net (code "92") (name "Net-(U23-IO42)") (class "Default")
      (node (ref "R47") (pin "1") (pinfunction "1_1") (pintype "passive"))
      (node (ref "U23") (pin "38") (pinfunction "IO42_38") (pintype "bidirectional"))
    )
    (net (code "93") (name "Net-(U27-~{INT})") (class "Default")
      (node (ref "R49") (pin "1") (pinfunction "1_1") (pintype "passive"))
      (node (ref "U27") (pin "11") (pinfunction "~{INT}_11") (pintype "open_collector"))
    )
    (net (code "94") (name "Net-(U28-HV)") (class "Default")
      (node (ref "C73") (pin "1") (pinfunction "1_1") (pintype "passive"))
      (node (ref "U28") (pin "D1") (pinfunction "HV_D1") (pintype "power_in"))
    )
    (net (code "95") (name "Net-(U28-PUMP)") (class "Default")
      (node (ref "C75") (pin "2") (pinfunction "2_2") (pintype "passive"))
      (node (ref "U28") (pin "A4") (pinfunction "PUMP_A4") (pintype "power_in"))
    )
    (net (code "96") (name "Net-(U28-REG)") (class "Default")
      (node (ref "C69") (pin "2") (pinfunction "2_2") (pintype "passive"))
      (node (ref "U28") (pin "B5") (pinfunction "REG_B5") (pintype "power_in"))
    )
    (net (code "97") (name "Net-(U28-RM)") (class "Default")
      (node (ref "L4") (pin "1") (pinfunction "1_1") (pintype "passive"))
      (node (ref "R64") (pin "2") (pinfunction "2_2") (pintype "passive"))
      (node (ref "U28") (pin "B4") (pinfunction "RM_B4") (pintype "input"))
    )
    (net (code "98") (name "Net-(U28-SDO)") (class "Default")
      (node (ref "R62") (pin "2") (pinfunction "2_2") (pintype "passive"))
      (node (ref "U28") (pin "C5") (pinfunction "SDO_C5") (pintype "output"))
    )
    (net (code "99") (name "Net-(U29-HV)") (class "Default")
      (node (ref "C74") (pin "1") (pinfunction "1_1") (pintype "passive"))
      (node (ref "U29") (pin "D1") (pinfunction "HV_D1") (pintype "power_in"))
    )
    (net (code "100") (name "Net-(U29-PUMP)") (class "Default")
      (node (ref "C76") (pin "2") (pinfunction "2_2") (pintype "passive"))
      (node (ref "U29") (pin "A4") (pinfunction "PUMP_A4") (pintype "power_in"))
    )
    (net (code "101") (name "Net-(U29-REG)") (class "Default")
      (node (ref "C70") (pin "2") (pinfunction "2_2") (pintype "passive"))
      (node (ref "U29") (pin "B5") (pinfunction "REG_B5") (pintype "power_in"))
    )
    (net (code "102") (name "Net-(U29-RM)") (class "Default")
      (node (ref "L5") (pin "1") (pinfunction "1_1") (pintype "passive"))
      (node (ref "R65") (pin "2") (pinfunction "2_2") (pintype "passive"))
      (node (ref "U29") (pin "B4") (pinfunction "RM_B4") (pintype "input"))
    )
    (net (code "103") (name "Net-(U29-SDO)") (class "Default")
      (node (ref "R63") (pin "2") (pinfunction "2_2") (pintype "passive"))
      (node (ref "U29") (pin "C5") (pinfunction "SDO_C5") (pintype "output"))
    )
    (net (code "104") (name "Net-(U30-HV)") (class "Default")
      (node (ref "C83") (pin "1") (pinfunction "1_1") (pintype "passive"))
      (node (ref "U30") (pin "D1") (pinfunction "HV_D1") (pintype "power_in"))
    )
    (net (code "105") (name "Net-(U30-PUMP)") (class "Default")
      (node (ref "C85") (pin "2") (pinfunction "2_2") (pintype "passive"))
      (node (ref "U30") (pin "A4") (pinfunction "PUMP_A4") (pintype "power_in"))
    )
    (net (code "106") (name "Net-(U30-REG)") (class "Default")
      (node (ref "C79") (pin "2") (pinfunction "2_2") (pintype "passive"))
      (node (ref "U30") (pin "B5") (pinfunction "REG_B5") (pintype "power_in"))
    )
    (net (code "107") (name "Net-(U30-RM)") (class "Default")
      (node (ref "L6") (pin "1") (pinfunction "1_1") (pintype "passive"))
      (node (ref "R68") (pin "2") (pinfunction "2_2") (pintype "passive"))
      (node (ref "U30") (pin "B4") (pinfunction "RM_B4") (pintype "input"))
    )
    (net (code "108") (name "Net-(U30-SDO)") (class "Default")
      (node (ref "R66") (pin "2") (pinfunction "2_2") (pintype "passive"))
      (node (ref "U30") (pin "C5") (pinfunction "SDO_C5") (pintype "output"))
    )
    (net (code "109") (name "Net-(U31-HV)") (class "Default")
      (node (ref "C84") (pin "1") (pinfunction "1_1") (pintype "passive"))
      (node (ref "U31") (pin "D1") (pinfunction "HV_D1") (pintype "power_in"))
    )
    (net (code "110") (name "Net-(U31-PUMP)") (class "Default")
      (node (ref "C86") (pin "2") (pinfunction "2_2") (pintype "passive"))
      (node (ref "U31") (pin "A4") (pinfunction "PUMP_A4") (pintype "power_in"))
    )
    (net (code "111") (name "Net-(U31-REG)") (class "Default")
      (node (ref "C80") (pin "2") (pinfunction "2_2") (pintype "passive"))
      (node (ref "U31") (pin "B5") (pinfunction "REG_B5") (pintype "power_in"))
    )
    (net (code "112") (name "Net-(U31-RM)") (class "Default")
      (node (ref "L7") (pin "1") (pinfunction "1_1") (pintype "passive"))
      (node (ref "R69") (pin "2") (pinfunction "2_2") (pintype "passive"))
      (node (ref "U31") (pin "B4") (pinfunction "RM_B4") (pintype "input"))
    )
    (net (code "113") (name "Net-(U31-SDO)") (class "Default")
      (node (ref "R67") (pin "2") (pinfunction "2_2") (pintype "passive"))
      (node (ref "U31") (pin "C5") (pinfunction "SDO_C5") (pintype "output"))
    )
    (net (code "114") (name "Net-(X1-OUT)") (class "Default")
      (node (ref "C52") (pin "1") (pinfunction "1_1") (pintype "passive"))
      (node (ref "X1") (pin "3") (pinfunction "OUT_3") (pintype "passive"))
    )
    (net (code "115") (name "unconnected-(J3-PadP1)") (class "Default")
      (node (ref "J3") (pin "P1") (pinfunction "P1_P1") (pintype "passive+no_connect"))
    )
    (net (code "116") (name "unconnected-(J3-PadP2)") (class "Default")
      (node (ref "J3") (pin "P2") (pinfunction "P2_P2") (pintype "passive+no_connect"))
    )
    (net (code "117") (name "unconnected-(J5-Pad46)") (class "Default")
      (node (ref "J5") (pin "46") (pinfunction "46_46") (pintype "passive+no_connect"))
    )
    (net (code "118") (name "unconnected-(J5-Pad47)") (class "Default")
      (node (ref "J5") (pin "47") (pinfunction "47_47") (pintype "passive+no_connect"))
    )
    (net (code "119") (name "unconnected-(LED4-DOUT-Pad2)") (class "Default")
      (node (ref "LED4") (pin "2") (pinfunction "DOUT_2") (pintype "output+no_connect"))
    )
    (net (code "120") (name "unconnected-(SW4-A-Pad1)") (class "Default")
      (node (ref "SW4") (pin "1") (pinfunction "A_1") (pintype "passive+no_connect"))
    )
    (net (code "121") (name "unconnected-(SW4-D-Pad4)") (class "Default")
      (node (ref "SW4") (pin "4") (pinfunction "D_4") (pintype "passive+no_connect"))
    )
    (net (code "122") (name "unconnected-(SW5-A-Pad1)") (class "Default")
      (node (ref "SW5") (pin "1") (pinfunction "A_1") (pintype "passive+no_connect"))
    )
    (net (code "123") (name "unconnected-(SW5-D-Pad4)") (class "Default")
      (node (ref "SW5") (pin "4") (pinfunction "D_4") (pintype "passive+no_connect"))
    )
    (net (code "124") (name "unconnected-(U23-IO16-Pad20)") (class "Default")
      (node (ref "U23") (pin "20") (pinfunction "IO16_20") (pintype "bidirectional+no_connect"))
    )
    (net (code "125") (name "unconnected-(U28-TST0-PadC2)") (class "Default")
      (node (ref "U28") (pin "C2") (pinfunction "TST0_C2") (pintype "passive+no_connect"))
    )
    (net (code "126") (name "unconnected-(U28-TST4-PadC3)") (class "Default")
      (node (ref "U28") (pin "C3") (pinfunction "TST4_C3") (pintype "passive+no_connect"))
    )
    (net (code "127") (name "unconnected-(U28-TST5-PadA3)") (class "Default")
      (node (ref "U28") (pin "A3") (pinfunction "TST5_A3") (pintype "passive+no_connect"))
    )
    (net (code "128") (name "unconnected-(U29-TST0-PadC2)") (class "Default")
      (node (ref "U29") (pin "C2") (pinfunction "TST0_C2") (pintype "passive+no_connect"))
    )
    (net (code "129") (name "unconnected-(U29-TST4-PadC3)") (class "Default")
      (node (ref "U29") (pin "C3") (pinfunction "TST4_C3") (pintype "passive+no_connect"))
    )
    (net (code "130") (name "unconnected-(U29-TST5-PadA3)") (class "Default")
      (node (ref "U29") (pin "A3") (pinfunction "TST5_A3") (pintype "passive+no_connect"))
    )
    (net (code "131") (name "unconnected-(U30-TST0-PadC2)") (class "Default")
      (node (ref "U30") (pin "C2") (pinfunction "TST0_C2") (pintype "passive+no_connect"))
    )
    (net (code "132") (name "unconnected-(U30-TST4-PadC3)") (class "Default")
      (node (ref "U30") (pin "C3") (pinfunction "TST4_C3") (pintype "passive+no_connect"))
    )
    (net (code "133") (name "unconnected-(U30-TST5-PadA3)") (class "Default")
      (node (ref "U30") (pin "A3") (pinfunction "TST5_A3") (pintype "passive+no_connect"))
    )
    (net (code "134") (name "unconnected-(U31-TST0-PadC2)") (class "Default")
      (node (ref "U31") (pin "C2") (pinfunction "TST0_C2") (pintype "passive+no_connect"))
    )
    (net (code "135") (name "unconnected-(U31-TST4-PadC3)") (class "Default")
      (node (ref "U31") (pin "C3") (pinfunction "TST4_C3") (pintype "passive+no_connect"))
    )
    (net (code "136") (name "unconnected-(U31-TST5-PadA3)") (class "Default")
      (node (ref "U31") (pin "A3") (pinfunction "TST5_A3") (pintype "passive+no_connect"))
    )
    (net (code "137") (name "unconnected-(X1-Enable{slash}Disable-Pad1)") (class "Default")
      (node (ref "X1") (pin "1") (pinfunction "Enable/Disable_1") (pintype "passive+no_connect"))
    )
  )
)
